# ESP-RC-Car-OLDPCB.net
KiCad netlist of a schematic drawn in Altium Designer
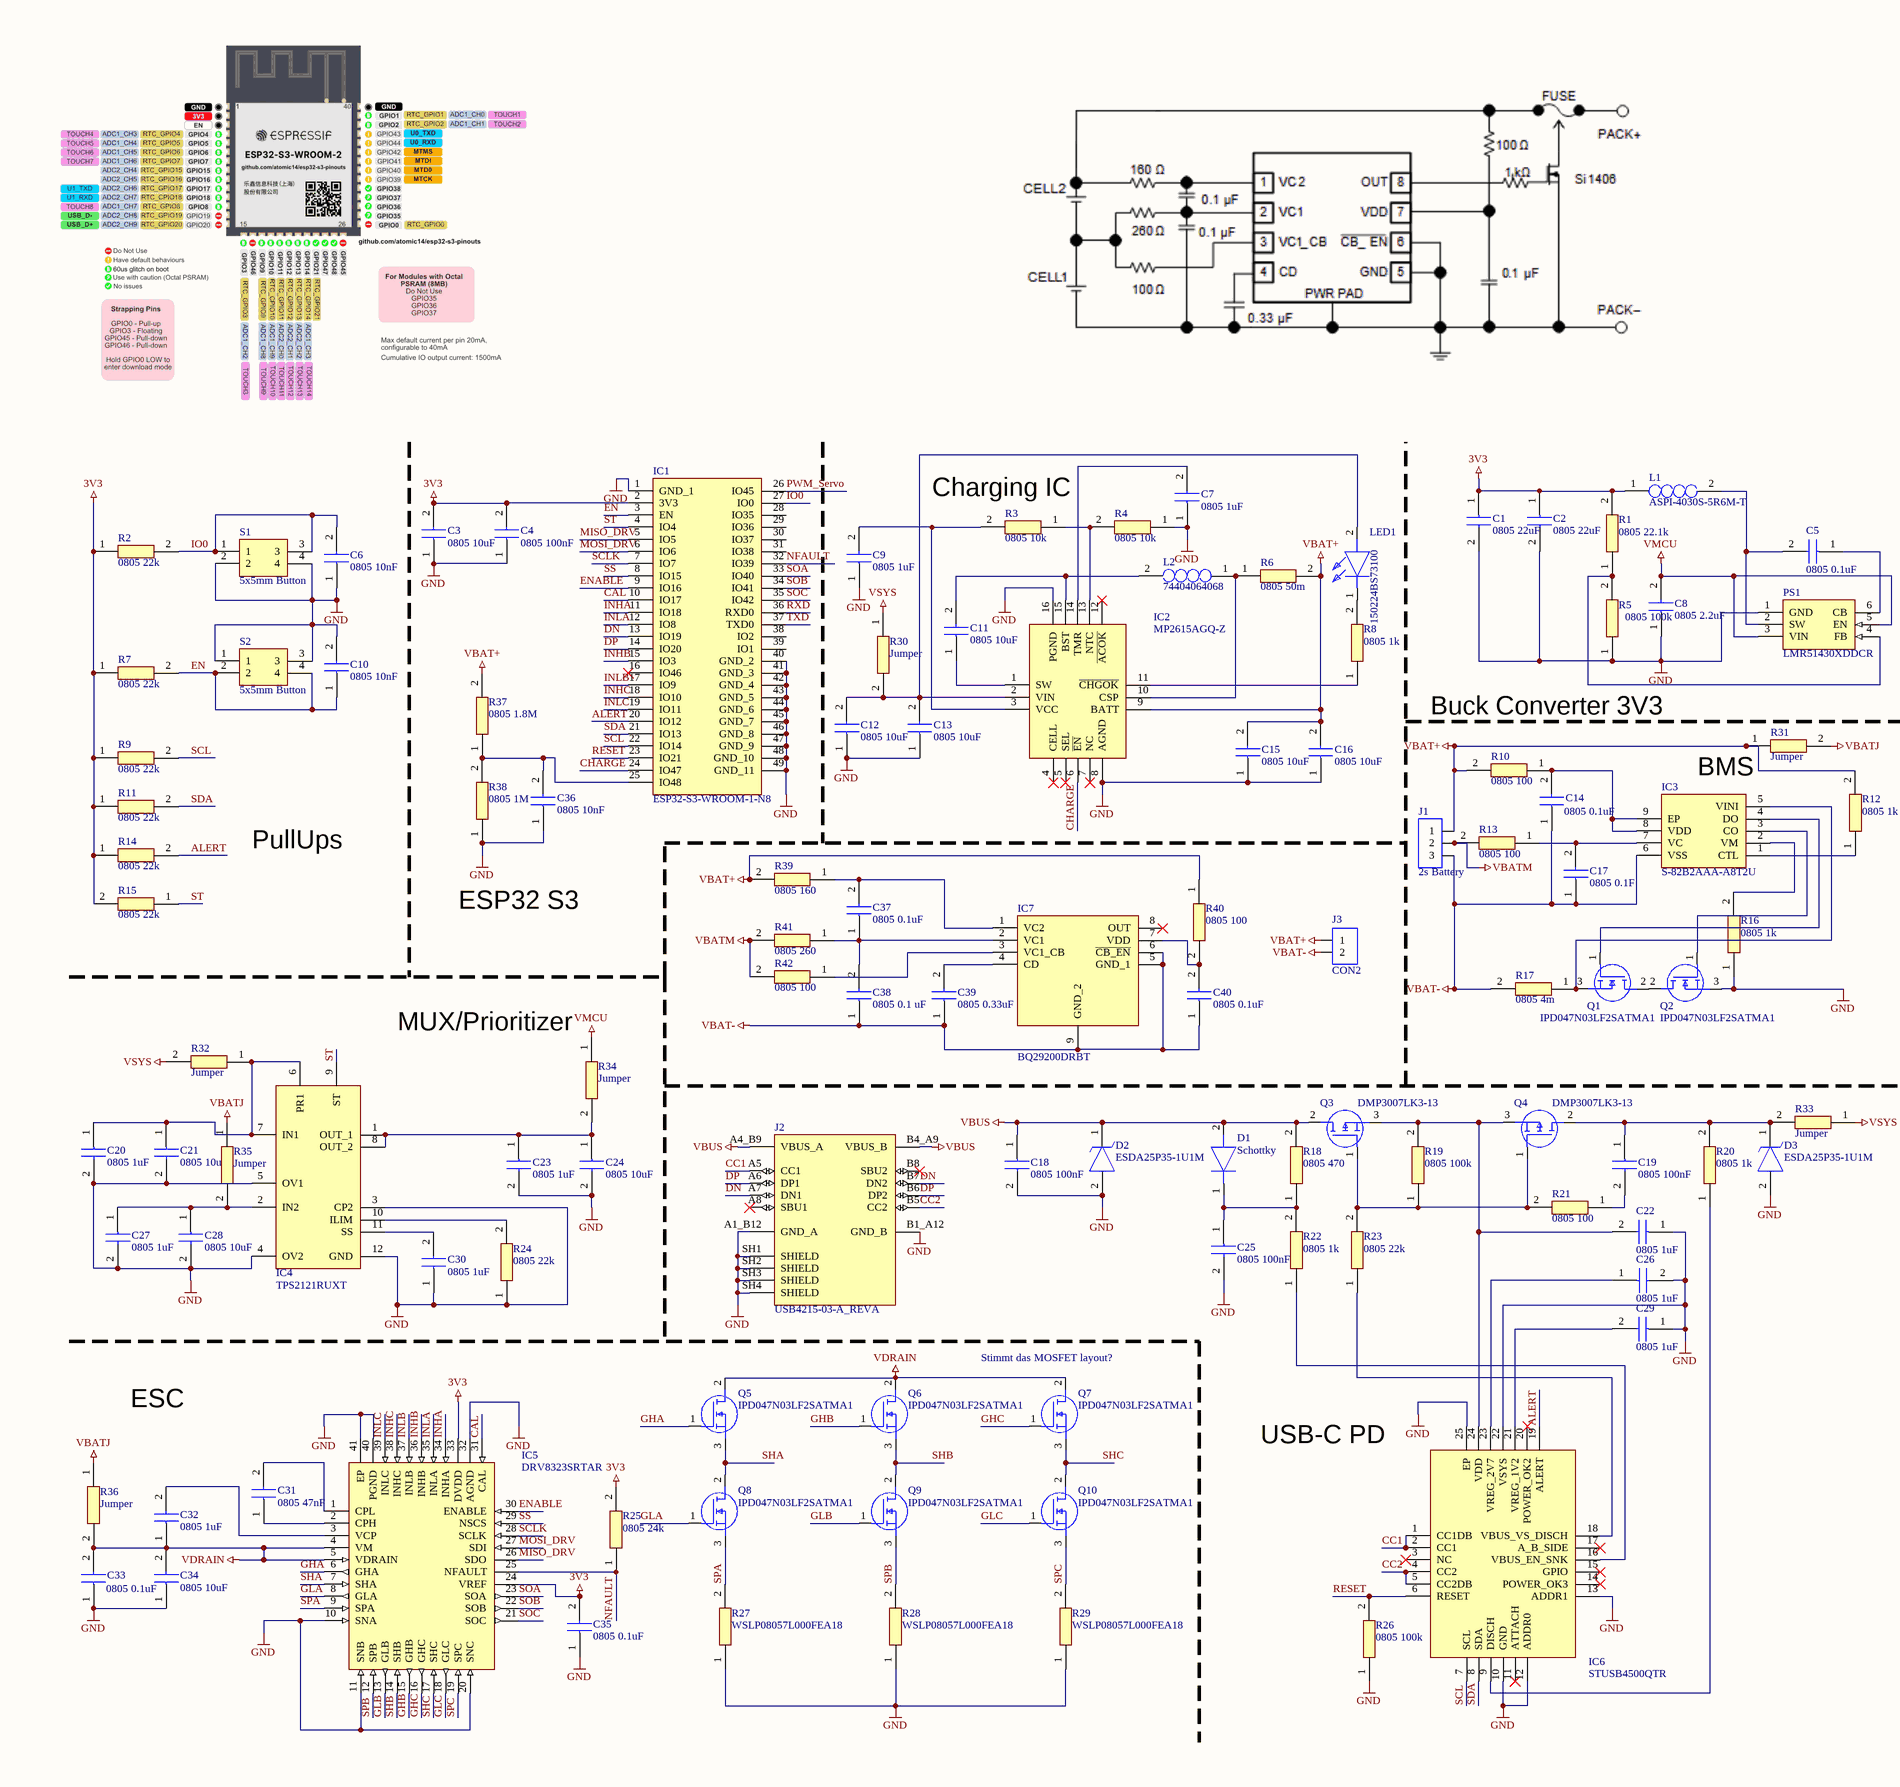
[diagram p0: ESP-RC-Car-OLDPCB.SchDoc, left]
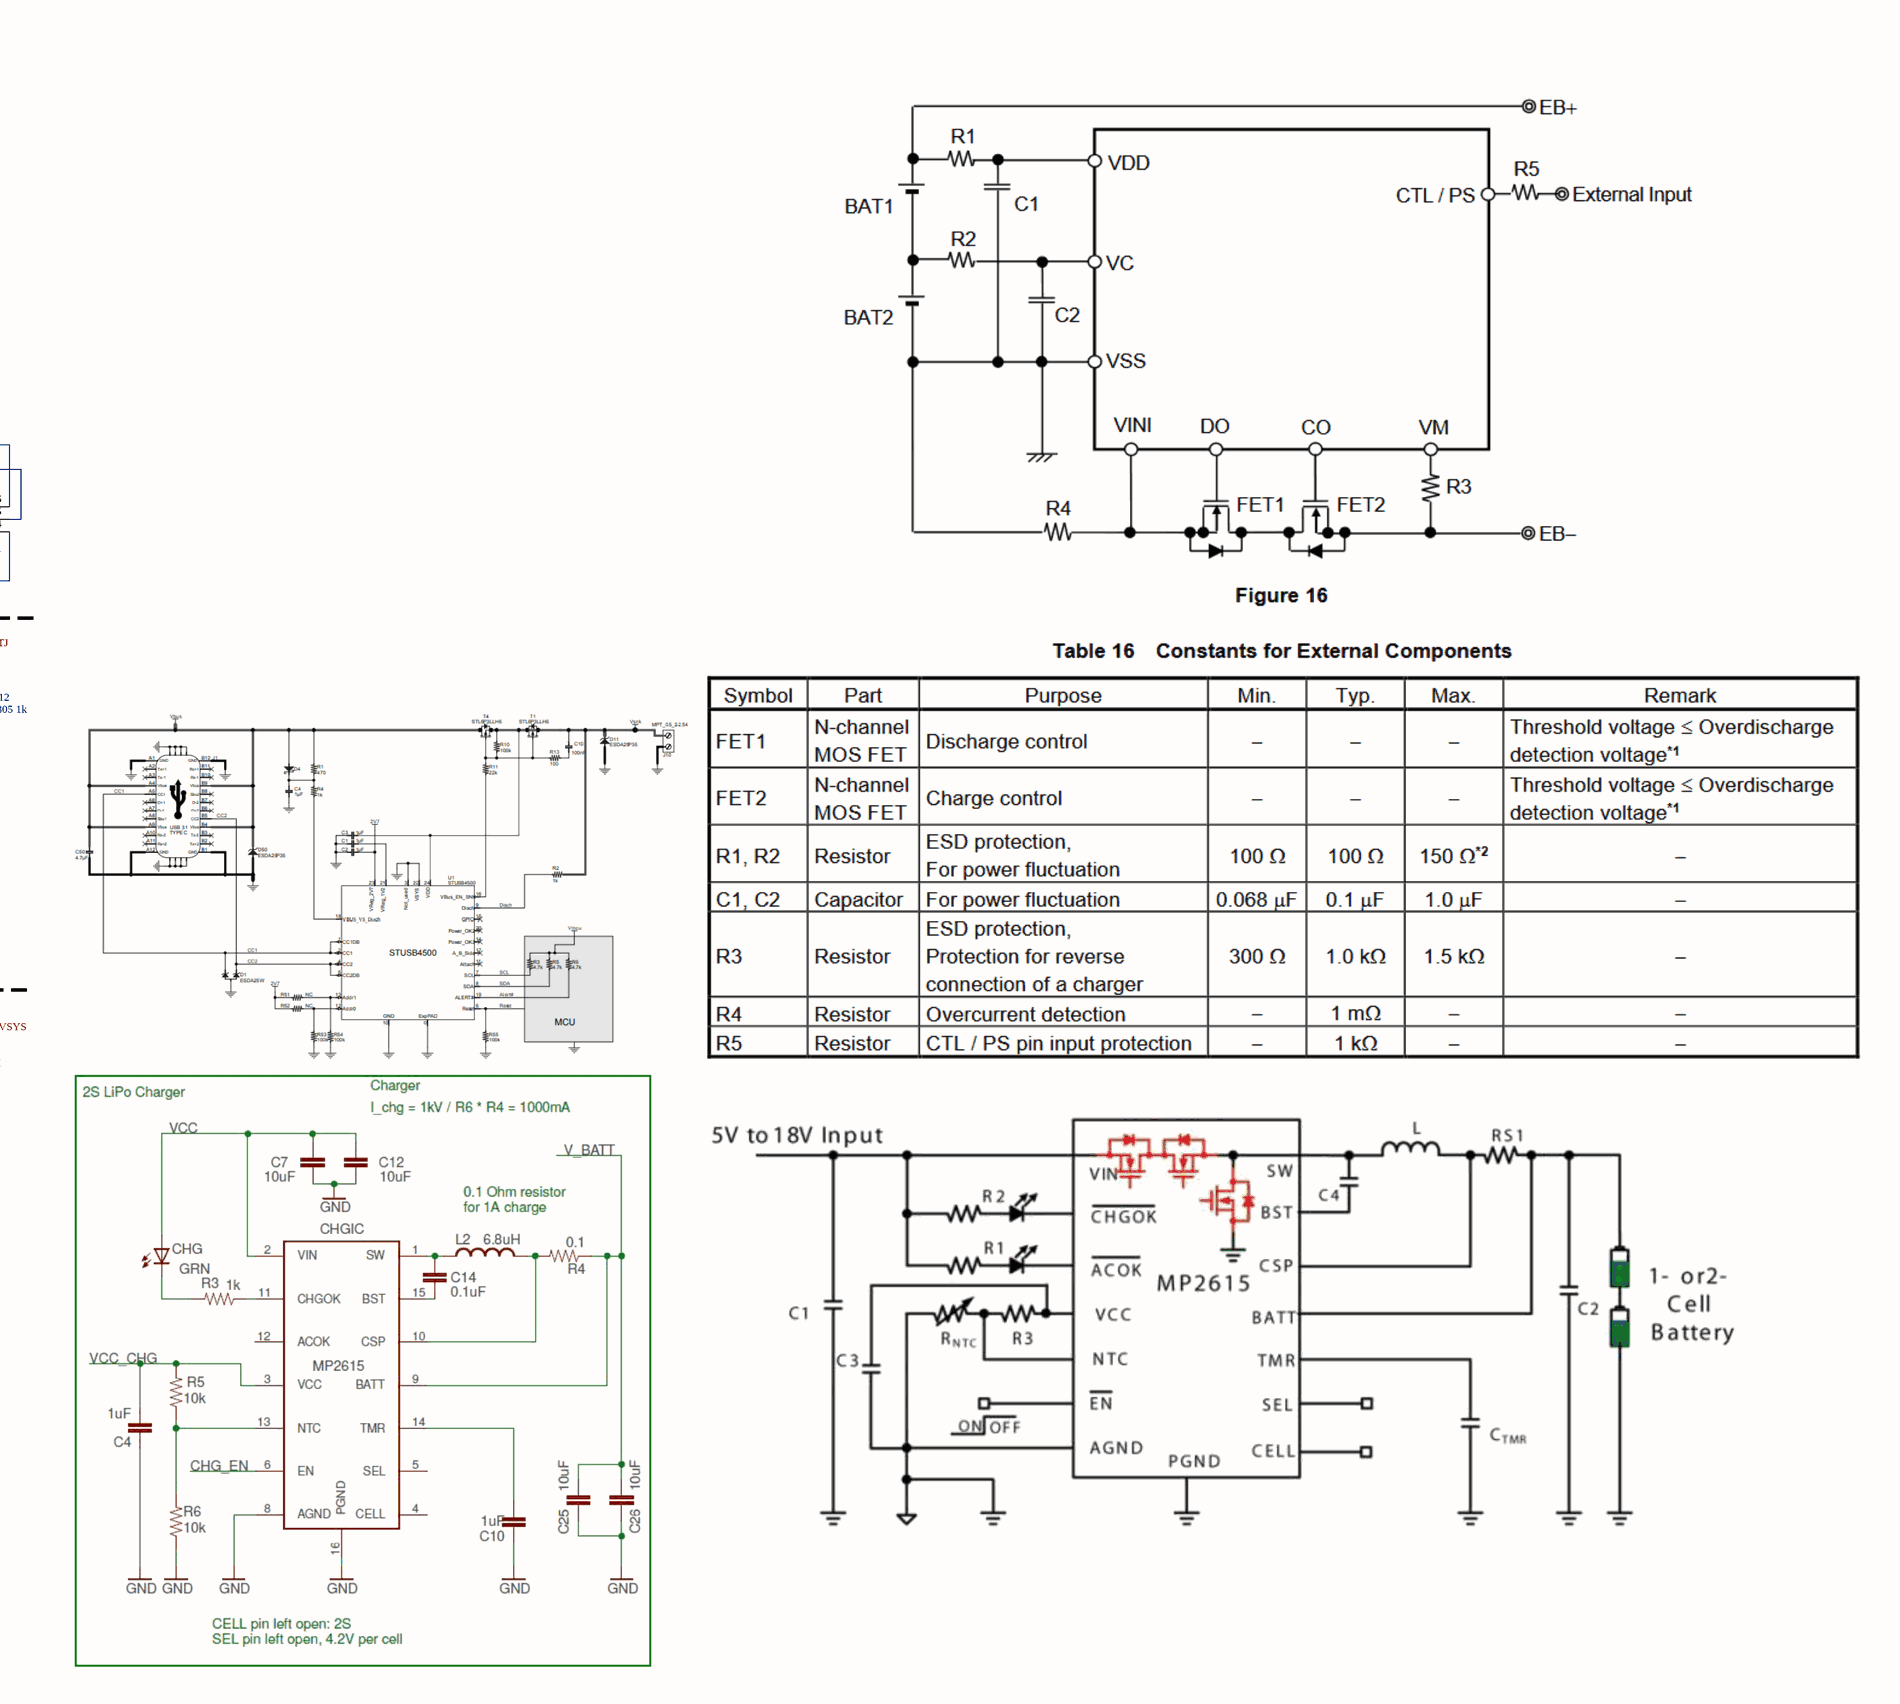
[diagram p1: ESP-RC-Car-OLDPCB.SchDoc, right]

(export (version "E")
  (design (tool "Eeschema 10.0.6"))
  (components
    (comp (ref "C1")
      (value "0805 22uF")
      (footprint "CAPC2012X94N")
      (description "Capacitor 25V")
      (fields
        (field (name "MANUFACTURER_PART_NUMBER") "08055A150JAT2A")
        (field (name "MOUSER PART NUMBER") "581-08055A150J")
      )
      (libsource (lib "*") (part "08055A150JAT2A"))
    )
    (comp (ref "C2")
      (value "0805 22uF")
      (footprint "CAPC2012X94N")
      (description "Capacitor 25V")
      (fields
        (field (name "MANUFACTURER_PART_NUMBER") "08055A150JAT2A")
        (field (name "MOUSER PART NUMBER") "581-08055A150J")
      )
      (libsource (lib "*") (part "08055A150JAT2A"))
    )
    (comp (ref "C3")
      (value "0805 10uF")
      (footprint "CAPC2012X94N")
      (description "Capacitor")
      (fields
        (field (name "MANUFACTURER_PART_NUMBER") "08055A150JAT2A")
        (field (name "MOUSER PART NUMBER") "581-08055A150J")
      )
      (libsource (lib "*") (part "08055A150JAT2A"))
    )
    (comp (ref "C4")
      (value "0805 100nF")
      (footprint "CAPC2012X94N")
      (description "Capacitor")
      (fields
        (field (name "MANUFACTURER_PART_NUMBER") "08055A150JAT2A")
        (field (name "MOUSER PART NUMBER") "581-08055A150J")
      )
      (libsource (lib "*") (part "08055A150JAT2A"))
    )
    (comp (ref "C5")
      (value "0805 0.1uF")
      (footprint "CAPC2012X94N")
      (description "Capacitor")
      (fields
        (field (name "MANUFACTURER_PART_NUMBER") "08055A150JAT2A")
        (field (name "MOUSER PART NUMBER") "581-08055A150J")
      )
      (libsource (lib "*") (part "08055A150JAT2A"))
    )
    (comp (ref "C6")
      (value "0805 10nF")
      (footprint "CAPC2012X94N")
      (description "Capacitor")
      (fields
        (field (name "MANUFACTURER_PART_NUMBER") "08055A150JAT2A")
        (field (name "MOUSER PART NUMBER") "581-08055A150J")
      )
      (libsource (lib "*") (part "08055A150JAT2A"))
    )
    (comp (ref "C7")
      (value "0805 1uF")
      (footprint "CAPC2012X94N")
      (description "Capacitor")
      (fields
        (field (name "MANUFACTURER_PART_NUMBER") "08055A150JAT2A")
        (field (name "MOUSER PART NUMBER") "581-08055A150J")
      )
      (libsource (lib "*") (part "08055A150JAT2A"))
    )
    (comp (ref "C8")
      (value "0805 2.2uF")
      (footprint "CAPC2012X94N")
      (description "Capacitor")
      (fields
        (field (name "MANUFACTURER_PART_NUMBER") "08055A150JAT2A")
        (field (name "MOUSER PART NUMBER") "581-08055A150J")
      )
      (libsource (lib "*") (part "08055A150JAT2A"))
    )
    (comp (ref "C9")
      (value "0805 1uF")
      (footprint "CAPC2012X94N")
      (description "Capacitor")
      (fields
        (field (name "MANUFACTURER_PART_NUMBER") "08055A150JAT2A")
        (field (name "MOUSER PART NUMBER") "581-08055A150J")
      )
      (libsource (lib "*") (part "08055A150JAT2A"))
    )
    (comp (ref "C10")
      (value "0805 10nF")
      (footprint "CAPC2012X94N")
      (description "Capacitor")
      (fields
        (field (name "MANUFACTURER_PART_NUMBER") "08055A150JAT2A")
        (field (name "MOUSER PART NUMBER") "581-08055A150J")
      )
      (libsource (lib "*") (part "08055A150JAT2A"))
    )
    (comp (ref "C11")
      (value "0805 10uF")
      (footprint "CAPC2012X94N")
      (description "Capacitor")
      (fields
        (field (name "MANUFACTURER_PART_NUMBER") "08055A150JAT2A")
        (field (name "MOUSER PART NUMBER") "581-08055A150J")
      )
      (libsource (lib "*") (part "08055A150JAT2A"))
    )
    (comp (ref "C12")
      (value "0805 10uF")
      (footprint "CAPC2012X94N")
      (description "Capacitor")
      (fields
        (field (name "MANUFACTURER_PART_NUMBER") "08055A150JAT2A")
        (field (name "MOUSER PART NUMBER") "581-08055A150J")
      )
      (libsource (lib "*") (part "08055A150JAT2A"))
    )
    (comp (ref "C13")
      (value "0805 10uF")
      (footprint "CAPC2012X94N")
      (description "Capacitor")
      (fields
        (field (name "MANUFACTURER_PART_NUMBER") "08055A150JAT2A")
        (field (name "MOUSER PART NUMBER") "581-08055A150J")
      )
      (libsource (lib "*") (part "08055A150JAT2A"))
    )
    (comp (ref "C14")
      (value "0805 0.1uF")
      (footprint "CAPC2012X94N")
      (description "Capacitor")
      (fields
        (field (name "MANUFACTURER_PART_NUMBER") "08055A150JAT2A")
        (field (name "MOUSER PART NUMBER") "581-08055A150J")
      )
      (libsource (lib "*") (part "08055A150JAT2A"))
    )
    (comp (ref "C15")
      (value "0805 10uF")
      (footprint "CAPC2012X94N")
      (description "Capacitor")
      (fields
        (field (name "MANUFACTURER_PART_NUMBER") "08055A150JAT2A")
        (field (name "MOUSER PART NUMBER") "581-08055A150J")
      )
      (libsource (lib "*") (part "08055A150JAT2A"))
    )
    (comp (ref "C16")
      (value "0805 10uF")
      (footprint "CAPC2012X94N")
      (description "Capacitor")
      (fields
        (field (name "MANUFACTURER_PART_NUMBER") "08055A150JAT2A")
        (field (name "MOUSER PART NUMBER") "581-08055A150J")
      )
      (libsource (lib "*") (part "08055A150JAT2A"))
    )
    (comp (ref "C17")
      (value "0805 0.1F")
      (footprint "CAPC2012X94N")
      (description "Capacitor")
      (fields
        (field (name "MANUFACTURER_PART_NUMBER") "08055A150JAT2A")
        (field (name "MOUSER PART NUMBER") "581-08055A150J")
      )
      (libsource (lib "*") (part "08055A150JAT2A"))
    )
    (comp (ref "C18")
      (value "0805 100nF")
      (footprint "CAPC2012X94N")
      (description "0805")
      (fields
        (field (name "MANUFACTURER_PART_NUMBER") "08055A150JAT2A")
        (field (name "MOUSER PART NUMBER") "581-08055A150J")
      )
      (libsource (lib "*") (part "08055A150JAT2A"))
    )
    (comp (ref "C19")
      (value "0805 100nF")
      (footprint "CAPC2012X94N")
      (description "0805")
      (fields
        (field (name "MANUFACTURER_PART_NUMBER") "08055A150JAT2A")
        (field (name "MOUSER PART NUMBER") "581-08055A150J")
      )
      (libsource (lib "*") (part "08055A150JAT2A"))
    )
    (comp (ref "C20")
      (value "0805 1uF")
      (footprint "CAPC2012X94N")
      (description "0805")
      (fields
        (field (name "MANUFACTURER_PART_NUMBER") "08055A150JAT2A")
        (field (name "MOUSER PART NUMBER") "581-08055A150J")
      )
      (libsource (lib "*") (part "08055A150JAT2A"))
    )
    (comp (ref "C21")
      (value "0805 10uF")
      (footprint "CAPC2012X94N")
      (description "0805")
      (fields
        (field (name "MANUFACTURER_PART_NUMBER") "08055A150JAT2A")
        (field (name "MOUSER PART NUMBER") "581-08055A150J")
      )
      (libsource (lib "*") (part "08055A150JAT2A"))
    )
    (comp (ref "C22")
      (value "0805 1uF")
      (footprint "CAPC2012X94N")
      (description "0805")
      (fields
        (field (name "MANUFACTURER_PART_NUMBER") "08055A150JAT2A")
        (field (name "MOUSER PART NUMBER") "581-08055A150J")
      )
      (libsource (lib "*") (part "08055A150JAT2A"))
    )
    (comp (ref "C23")
      (value "0805 1uF")
      (footprint "CAPC2012X94N")
      (description "0805")
      (fields
        (field (name "MANUFACTURER_PART_NUMBER") "08055A150JAT2A")
        (field (name "MOUSER PART NUMBER") "581-08055A150J")
      )
      (libsource (lib "*") (part "08055A150JAT2A"))
    )
    (comp (ref "C24")
      (value "0805 10uF")
      (footprint "CAPC2012X94N")
      (description "0805")
      (fields
        (field (name "MANUFACTURER_PART_NUMBER") "08055A150JAT2A")
        (field (name "MOUSER PART NUMBER") "581-08055A150J")
      )
      (libsource (lib "*") (part "08055A150JAT2A"))
    )
    (comp (ref "C25")
      (value "0805 100nF")
      (footprint "CAPC2012X94N")
      (description "0805")
      (fields
        (field (name "MANUFACTURER_PART_NUMBER") "08055A150JAT2A")
        (field (name "MOUSER PART NUMBER") "581-08055A150J")
      )
      (libsource (lib "*") (part "08055A150JAT2A"))
    )
    (comp (ref "C26")
      (value "0805 1uF")
      (footprint "CAPC2012X94N")
      (description "0805")
      (fields
        (field (name "MANUFACTURER_PART_NUMBER") "08055A150JAT2A")
        (field (name "MOUSER PART NUMBER") "581-08055A150J")
      )
      (libsource (lib "*") (part "08055A150JAT2A"))
    )
    (comp (ref "C27")
      (value "0805 1uF")
      (footprint "CAPC2012X94N")
      (description "0805")
      (fields
        (field (name "MANUFACTURER_PART_NUMBER") "08055A150JAT2A")
        (field (name "MOUSER PART NUMBER") "581-08055A150J")
      )
      (libsource (lib "*") (part "08055A150JAT2A"))
    )
    (comp (ref "C28")
      (value "0805 10uF")
      (footprint "CAPC2012X94N")
      (description "0805")
      (fields
        (field (name "MANUFACTURER_PART_NUMBER") "08055A150JAT2A")
        (field (name "MOUSER PART NUMBER") "581-08055A150J")
      )
      (libsource (lib "*") (part "08055A150JAT2A"))
    )
    (comp (ref "C29")
      (value "0805 1uF")
      (footprint "CAPC2012X94N")
      (description "0805")
      (fields
        (field (name "MANUFACTURER_PART_NUMBER") "08055A150JAT2A")
        (field (name "MOUSER PART NUMBER") "581-08055A150J")
      )
      (libsource (lib "*") (part "08055A150JAT2A"))
    )
    (comp (ref "C30")
      (value "0805 1uF")
      (footprint "CAPC2012X94N")
      (description "0805")
      (fields
        (field (name "MANUFACTURER_PART_NUMBER") "08055A150JAT2A")
        (field (name "MOUSER PART NUMBER") "581-08055A150J")
      )
      (libsource (lib "*") (part "08055A150JAT2A"))
    )
    (comp (ref "C31")
      (value "0805 47nF")
      (footprint "CAPC2012X94N")
      (description "0805")
      (fields
        (field (name "MANUFACTURER_PART_NUMBER") "08055A150JAT2A")
        (field (name "MOUSER PART NUMBER") "581-08055A150J")
      )
      (libsource (lib "*") (part "08055A150JAT2A"))
    )
    (comp (ref "C32")
      (value "0805 1uF")
      (footprint "CAPC2012X94N")
      (description "0805 16V X5R/X7R")
      (fields
        (field (name "MANUFACTURER_PART_NUMBER") "08055A150JAT2A")
        (field (name "MOUSER PART NUMBER") "581-08055A150J")
      )
      (libsource (lib "*") (part "08055A150JAT2A"))
    )
    (comp (ref "C33")
      (value "0805 0.1uF")
      (footprint "CAPC2012X94N")
      (description "0805 VM rated")
      (fields
        (field (name "MANUFACTURER_PART_NUMBER") "08055A150JAT2A")
        (field (name "MOUSER PART NUMBER") "581-08055A150J")
      )
      (libsource (lib "*") (part "08055A150JAT2A"))
    )
    (comp (ref "C34")
      (value "0805 10uF")
      (footprint "CAPC2012X94N")
      (description "0805")
      (fields
        (field (name "MANUFACTURER_PART_NUMBER") "08055A150JAT2A")
        (field (name "MOUSER PART NUMBER") "581-08055A150J")
      )
      (libsource (lib "*") (part "08055A150JAT2A"))
    )
    (comp (ref "C35")
      (value "0805 0.1uF")
      (footprint "CAPC2012X94N")
      (description "0805")
      (fields
        (field (name "MANUFACTURER_PART_NUMBER") "08055A150JAT2A")
        (field (name "MOUSER PART NUMBER") "581-08055A150J")
      )
      (libsource (lib "*") (part "08055A150JAT2A"))
    )
    (comp (ref "C36")
      (value "0805 10nF")
      (footprint "CAPC2012X94N")
      (description "Capacitor")
      (fields
        (field (name "MANUFACTURER_PART_NUMBER") "08055A150JAT2A")
        (field (name "MOUSER PART NUMBER") "581-08055A150J")
      )
      (libsource (lib "*") (part "08055A150JAT2A"))
    )
    (comp (ref "C37")
      (value "0805 0.1uF")
      (footprint "CAPC2012X94N")
      (description "Capacitor")
      (fields
        (field (name "MANUFACTURER_PART_NUMBER") "08055A150JAT2A")
        (field (name "MOUSER PART NUMBER") "581-08055A150J")
      )
      (libsource (lib "*") (part "08055A150JAT2A"))
    )
    (comp (ref "C38")
      (value "0805 0.1 uF")
      (footprint "CAPC2012X94N")
      (description "Capacitor")
      (fields
        (field (name "MANUFACTURER_PART_NUMBER") "08055A150JAT2A")
        (field (name "MOUSER PART NUMBER") "581-08055A150J")
      )
      (libsource (lib "*") (part "08055A150JAT2A"))
    )
    (comp (ref "C39")
      (value "0805 0.33uF")
      (footprint "CAPC2012X94N")
      (description "Capacitor")
      (fields
        (field (name "MANUFACTURER_PART_NUMBER") "08055A150JAT2A")
        (field (name "MOUSER PART NUMBER") "581-08055A150J")
      )
      (libsource (lib "*") (part "08055A150JAT2A"))
    )
    (comp (ref "C40")
      (value "0805 0.1uF")
      (footprint "CAPC2012X94N")
      (description "Capacitor")
      (fields
        (field (name "MANUFACTURER_PART_NUMBER") "08055A150JAT2A")
        (field (name "MOUSER PART NUMBER") "581-08055A150J")
      )
      (libsource (lib "*") (part "08055A150JAT2A"))
    )
    (comp (ref "D1")
      (value "Schottky")
      (footprint "SODFL3517X110N")
      (description "Schottky Diode")
      (fields (field (name "MANUFACTURER_PART_NUMBER") "PMEG3010ER"))
      (libsource (lib "*") (part "PMEG3010ER"))
    )
    (comp (ref "D2")
      (value "ESDA25P35-1U1M")
      (footprint "ESDA25P351U1M")
      (description "TVS Diode (Uni-directional)")
      (fields (field (name "MOUSER PART NUMBER") "511-ESDA25P35-1U1M"))
      (libsource (lib "*") (part "ESDA25P35-1U1M"))
    )
    (comp (ref "D3")
      (value "ESDA25P35-1U1M")
      (footprint "ESDA25P351U1M")
      (description "TVS Diode (Uni-directional)")
      (fields (field (name "MOUSER PART NUMBER") "511-ESDA25P35-1U1M"))
      (libsource (lib "*") (part "ESDA25P35-1U1M"))
    )
    (comp (ref "IC1")
      (value "ESP32-S3-WROOM-1-N8")
      (footprint "ESP32S3WROOM1N8R2")
      (description "Integrated Circuit")
      (fields (field (name "MOUSER PART NUMBER") "356-ESP32-S3WROOM1N8"))
      (libsource (lib "*") (part "ESP32-S3-WROOM-1-N8"))
    )
    (comp (ref "IC2")
      (value "MP2615AGQ-Z")
      (footprint "MP2615AGQZ")
      (description "Integrated Circuit")
      (fields (field (name "MOUSER PART NUMBER") "946-MP2615AGQ-Z"))
      (libsource (lib "*") (part "MP2615AGQ-Z"))
    )
    (comp (ref "IC3")
      (value "S-82B2AAA-A8T2U")
      (footprint "S82B2AAAA8T2U")
      (description "Integrated Circuit")
      (fields (field (name "MOUSER PART NUMBER") "628-S-82B2AAA-A8T2U"))
      (libsource (lib "*") (part "S-82B2AAA-A8T2U"))
    )
    (comp (ref "IC4")
      (value "TPS2121RUXT")
      (footprint "TPS2121RUXT")
      (description "Integrated Circuit")
      (fields (field (name "MOUSER PART NUMBER") "595-TPS2121RUXT"))
      (libsource (lib "*") (part "TPS2121RUXT"))
    )
    (comp (ref "IC5")
      (value "DRV8323SRTAR")
      (footprint "QFN50P600X600X80-41N-D")
      (description "Integrated Circuit")
      (fields (field (name "MOUSER PART NUMBER") "595-DRV8323SRTAR"))
      (libsource (lib "lib") (part "DRV8323SRTAR"))
    )
    (comp (ref "IC6")
      (value "STUSB4500QTR")
      (footprint "QFN50P400X400X100-25N-D")
      (description "Integrated Circuit")
      (fields (field (name "MOUSER PART NUMBER") "511-STUSB4500QTR"))
      (libsource (lib "*") (part "STUSB4500QTR"))
    )
    (comp (ref "IC7")
      (value "BQ29200DRBT")
      (footprint "SON65P300X300X100-9N-D")
      (description "Integrated Circuit")
      (fields (field (name "MOUSER PART NUMBER") "595-BQ29200DRBT"))
      (libsource (lib "*") (part "BQ29200DRBT"))
    )
    (comp (ref "J1")
      (value "2s Battery")
      (footprint "Sip-3")
      (description "Stecker")
      (libsource (lib "lib") (part "CON3"))
    )
    (comp (ref "J2")
      (value "USB4215-03-A_REVA")
      (footprint "GCT_USB4215-03-A_REVA")
      (fields (field (name "MF") "Global Connector Technology") (field (name "MP") "USB4215-03-A"))
      (libsource (lib "lib") (part "USB4215-03-A_REVA"))
    )
    (comp (ref "J3")
      (value "CON2")
      (footprint "SIP-2")
      (description "Stecker")
      (libsource (lib "lib") (part "CON2"))
    )
    (comp (ref "L1")
      (value "ASPI-4030S-5R6M-T")
      (footprint "ASPI-4030S")
      (description "Inductor")
      (fields (field (name "MOUSER PART NUMBER") "815-ASPI-4030S-5R6MT"))
      (libsource (lib "*") (part "ASPI-4030S-5R6M-T"))
    )
    (comp (ref "L2")
      (value "74404064068")
      (footprint "INDPM6060X450N")
      (description "Inductor")
      (fields (field (name "MOUSER PART NUMBER") "710-74404064068"))
      (libsource (lib "*") (part "74404064068"))
    )
    (comp (ref "LED1")
      (value "150224BS73100")
      (footprint "150224BS73100")
      (description "LED")
      (fields (field (name "MOUSER PART NUMBER") "710-150224BS73100"))
      (libsource (lib "*") (part "150224BS73100"))
    )
    (comp (ref "PS1")
      (value "LMR51430XDDCR")
      (footprint "SOT95P280X110-6N")
      (description "Power Supply 500kHz")
      (fields (field (name "MOUSER PART NUMBER") "595-LMR51430XDDCR"))
      (libsource (lib "*") (part "LMR51430XDDCR"))
    )
    (comp (ref "Q1")
      (value "IPD047N03LF2SATMA1")
      (footprint "IPD047N03LF2SATMA1")
      (description "MOSFET (N-Channel)")
      (fields (field (name "MOUSER PART NUMBER") "726-IPD047N03LF2SATM"))
      (libsource (lib "*") (part "IPD047N03LF2SATMA1"))
    )
    (comp (ref "Q2")
      (value "IPD047N03LF2SATMA1")
      (footprint "IPD047N03LF2SATMA1")
      (description "MOSFET (N-Channel)")
      (fields (field (name "MOUSER PART NUMBER") "726-IPD047N03LF2SATM"))
      (libsource (lib "*") (part "IPD047N03LF2SATMA1"))
    )
    (comp (ref "Q3")
      (value "DMP3007LK3-13")
      (footprint "DMP3007LK313")
      (description "MOSFET (P-Channel)")
      (fields (field (name "MOUSER PART NUMBER") "621-DMP3007LK3-13"))
      (libsource (lib "*") (part "DMP3007LK3-13"))
    )
    (comp (ref "Q4")
      (value "DMP3007LK3-13")
      (footprint "DMP3007LK313")
      (description "MOSFET (P-Channel)")
      (fields (field (name "MOUSER PART NUMBER") "621-DMP3007LK3-13"))
      (libsource (lib "*") (part "DMP3007LK3-13"))
    )
    (comp (ref "Q5")
      (value "IPD047N03LF2SATMA1")
      (footprint "IPD047N03LF2SATMA1")
      (description "MOSFET (N-Channel)")
      (fields (field (name "MOUSER PART NUMBER") "726-IPD047N03LF2SATM"))
      (libsource (lib "*") (part "IPD047N03LF2SATMA1"))
    )
    (comp (ref "Q6")
      (value "IPD047N03LF2SATMA1")
      (footprint "IPD047N03LF2SATMA1")
      (description "MOSFET (N-Channel)")
      (fields (field (name "MOUSER PART NUMBER") "726-IPD047N03LF2SATM"))
      (libsource (lib "*") (part "IPD047N03LF2SATMA1"))
    )
    (comp (ref "Q7")
      (value "IPD047N03LF2SATMA1")
      (footprint "IPD047N03LF2SATMA1")
      (description "MOSFET (N-Channel)")
      (fields (field (name "MOUSER PART NUMBER") "726-IPD047N03LF2SATM"))
      (libsource (lib "*") (part "IPD047N03LF2SATMA1"))
    )
    (comp (ref "Q8")
      (value "IPD047N03LF2SATMA1")
      (footprint "IPD047N03LF2SATMA1")
      (description "MOSFET (N-Channel)")
      (fields (field (name "MOUSER PART NUMBER") "726-IPD047N03LF2SATM"))
      (libsource (lib "*") (part "IPD047N03LF2SATMA1"))
    )
    (comp (ref "Q9")
      (value "IPD047N03LF2SATMA1")
      (footprint "IPD047N03LF2SATMA1")
      (description "MOSFET (N-Channel)")
      (fields (field (name "MOUSER PART NUMBER") "726-IPD047N03LF2SATM"))
      (libsource (lib "*") (part "IPD047N03LF2SATMA1"))
    )
    (comp (ref "Q10")
      (value "IPD047N03LF2SATMA1")
      (footprint "IPD047N03LF2SATMA1")
      (description "MOSFET (N-Channel)")
      (fields (field (name "MOUSER PART NUMBER") "726-IPD047N03LF2SATM"))
      (libsource (lib "*") (part "IPD047N03LF2SATMA1"))
    )
    (comp (ref "R1")
      (value "0805 22.1k")
      (footprint "RESC2012X65N")
      (description "Resistor low tolerance")
      (fields (field (name "MANUFACTURER_PART_NUMBER") "CPF0805B102RE1"))
      (libsource (lib "") (part "CPF0805B102RE1_2"))
    )
    (comp (ref "R2")
      (value "0805 22k")
      (footprint "RESC2012X65N")
      (description "Resistor")
      (fields (field (name "MANUFACTURER_PART_NUMBER") "CPF0805B102RE1"))
      (libsource (lib "") (part "CPF0805B102RE1_3"))
    )
    (comp (ref "R3")
      (value "0805 10k")
      (footprint "RESC2012X65N")
      (description "Resistor low tolerance")
      (fields (field (name "MANUFACTURER_PART_NUMBER") "CPF0805B102RE1"))
      (libsource (lib "") (part "CPF0805B102RE1_1"))
    )
    (comp (ref "R4")
      (value "0805 10k")
      (footprint "RESC2012X65N")
      (description "Resistor low tolerance")
      (fields (field (name "MANUFACTURER_PART_NUMBER") "CPF0805B102RE1"))
      (libsource (lib "") (part "CPF0805B102RE1_1"))
    )
    (comp (ref "R5")
      (value "0805 100k")
      (footprint "RESC2012X65N")
      (description "Resistor low tolerance")
      (fields (field (name "MANUFACTURER_PART_NUMBER") "CPF0805B102RE1"))
      (libsource (lib "") (part "CPF0805B102RE1_2"))
    )
    (comp (ref "R6")
      (value "0805 50m")
      (footprint "RESC2012X65N")
      (description "Resistor low tolerance")
      (fields (field (name "MANUFACTURER_PART_NUMBER") "CPF0805B102RE1"))
      (libsource (lib "") (part "CPF0805B102RE1_3"))
    )
    (comp (ref "R7")
      (value "0805 22k")
      (footprint "RESC2012X65N")
      (description "Resistor")
      (fields (field (name "MANUFACTURER_PART_NUMBER") "CPF0805B102RE1"))
      (libsource (lib "") (part "CPF0805B102RE1_3"))
    )
    (comp (ref "R8")
      (value "0805 1k")
      (footprint "RESC2012X65N")
      (description "Resistor low tolerance")
      (fields (field (name "MANUFACTURER_PART_NUMBER") "CPF0805B102RE1"))
      (libsource (lib "") (part "CPF0805B102RE1_2"))
    )
    (comp (ref "R9")
      (value "0805 22k")
      (footprint "RESC2012X65N")
      (description "Resistor")
      (fields (field (name "MANUFACTURER_PART_NUMBER") "CPF0805B102RE1"))
      (libsource (lib "") (part "CPF0805B102RE1_3"))
    )
    (comp (ref "R10")
      (value "0805 100")
      (footprint "RESC2012X65N")
      (description "Resistor low tolerance")
      (fields (field (name "MANUFACTURER_PART_NUMBER") "CPF0805B102RE1"))
      (libsource (lib "") (part "CPF0805B102RE1_1"))
    )
    (comp (ref "R11")
      (value "0805 22k")
      (footprint "RESC2012X65N")
      (description "Resistor")
      (fields (field (name "MANUFACTURER_PART_NUMBER") "CPF0805B102RE1"))
      (libsource (lib "") (part "CPF0805B102RE1_3"))
    )
    (comp (ref "R12")
      (value "0805 1k")
      (footprint "RESC2012X65N")
      (description "Resistor low tolerance")
      (fields (field (name "MANUFACTURER_PART_NUMBER") "CPF0805B102RE1"))
      (libsource (lib "") (part "CPF0805B102RE1_2"))
    )
    (comp (ref "R13")
      (value "0805 100")
      (footprint "RESC2012X65N")
      (description "Resistor low tolerance")
      (fields (field (name "MANUFACTURER_PART_NUMBER") "CPF0805B102RE1"))
      (libsource (lib "") (part "CPF0805B102RE1_1"))
    )
    (comp (ref "R14")
      (value "0805 22k")
      (footprint "RESC2012X65N")
      (description "Resistor")
      (fields (field (name "MANUFACTURER_PART_NUMBER") "CPF0805B102RE1"))
      (libsource (lib "") (part "CPF0805B102RE1_3"))
    )
    (comp (ref "R15")
      (value "0805 22k")
      (footprint "RESC2012X65N")
      (description "Resistor")
      (fields (field (name "MANUFACTURER_PART_NUMBER") "CPF0805B102RE1"))
      (libsource (lib "") (part "CPF0805B102RE1_1"))
    )
    (comp (ref "R16")
      (value "0805 1k")
      (footprint "RESC2012X65N")
      (description "Resistor low tolerance")
      (fields (field (name "MANUFACTURER_PART_NUMBER") "CPF0805B102RE1"))
      (libsource (lib "") (part "CPF0805B102RE1_2"))
    )
    (comp (ref "R17")
      (value "0805 4m")
      (footprint "RESC2012X65N")
      (description "Resistor low tolerance")
      (fields (field (name "MANUFACTURER_PART_NUMBER") "CPF0805B102RE1"))
      (libsource (lib "") (part "CPF0805B102RE1_1"))
    )
    (comp (ref "R18")
      (value "0805 470")
      (footprint "RESC2012X65N")
      (description "Resistor")
      (fields (field (name "MANUFACTURER_PART_NUMBER") "CPF0805B102RE1"))
      (libsource (lib "") (part "CPF0805B102RE1_2"))
    )
    (comp (ref "R19")
      (value "0805 100k")
      (footprint "RESC2012X65N")
      (description "Resistor")
      (fields (field (name "MANUFACTURER_PART_NUMBER") "CPF0805B102RE1"))
      (libsource (lib "") (part "CPF0805B102RE1_2"))
    )
    (comp (ref "R20")
      (value "0805 1k")
      (footprint "RESC2012X65N")
      (description "Resistor")
      (fields (field (name "MANUFACTURER_PART_NUMBER") "CPF0805B102RE1"))
      (libsource (lib "") (part "CPF0805B102RE1_2"))
    )
    (comp (ref "R21")
      (value "0805 100")
      (footprint "RESC2012X65N")
      (description "Resistor")
      (fields (field (name "MANUFACTURER_PART_NUMBER") "CPF0805B102RE1"))
      (libsource (lib "") (part "CPF0805B102RE1_1"))
    )
    (comp (ref "R22")
      (value "0805 1k")
      (footprint "RESC2012X65N")
      (description "Resistor")
      (fields (field (name "MANUFACTURER_PART_NUMBER") "CPF0805B102RE1"))
      (libsource (lib "") (part "CPF0805B102RE1_2"))
    )
    (comp (ref "R23")
      (value "0805 22k")
      (footprint "RESC2012X65N")
      (description "Resistor")
      (fields (field (name "MANUFACTURER_PART_NUMBER") "CPF0805B102RE1"))
      (libsource (lib "") (part "CPF0805B102RE1_2"))
    )
    (comp (ref "R24")
      (value "0805 22k")
      (footprint "RESC2012X65N")
      (description "Resistor")
      (fields (field (name "MANUFACTURER_PART_NUMBER") "CPF0805B102RE1"))
      (libsource (lib "") (part "CPF0805B102RE1_2"))
    )
    (comp (ref "R25")
      (value "0805 24k")
      (footprint "RESC2012X65N")
      (description "Resistor")
      (fields (field (name "MANUFACTURER_PART_NUMBER") "CPF0805B102RE1"))
      (libsource (lib "") (part "CPF0805B102RE1_2"))
    )
    (comp (ref "R26")
      (value "0805 100k")
      (footprint "RESC2012X65N")
      (description "Resistor")
      (fields (field (name "MANUFACTURER_PART_NUMBER") "CPF0805B102RE1"))
      (libsource (lib "") (part "CPF0805B102RE1_2"))
    )
    (comp (ref "R27")
      (value "WSLP08057L000FEA18")
      (footprint "RESC2013X58N")
      (description "Resistor")
      (fields (field (name "MOUSER PART NUMBER") "71-WSLP08057L000FEA1"))
      (libsource (lib "*") (part "WSLP08057L000FEA18"))
    )
    (comp (ref "R28")
      (value "WSLP08057L000FEA18")
      (footprint "RESC2013X58N")
      (description "Resistor")
      (fields (field (name "MOUSER PART NUMBER") "71-WSLP08057L000FEA1"))
      (libsource (lib "*") (part "WSLP08057L000FEA18"))
    )
    (comp (ref "R29")
      (value "WSLP08057L000FEA18")
      (footprint "RESC2013X58N")
      (description "Resistor")
      (fields (field (name "MOUSER PART NUMBER") "71-WSLP08057L000FEA1"))
      (libsource (lib "*") (part "WSLP08057L000FEA18"))
    )
    (comp (ref "R30")
      (value "Jumper")
      (footprint "Solder Jumper 5A")
      (description "Resistor")
      (fields (field (name "MANUFACTURER_PART_NUMBER") "CPF0805B102RE1"))
      (libsource (lib "*") (part "CPF0805B102RE1"))
    )
    (comp (ref "R31")
      (value "Jumper")
      (footprint "Solder Jumper 9A")
      (description "Resistor")
      (fields (field (name "MANUFACTURER_PART_NUMBER") "CPF0805B102RE1"))
      (libsource (lib "") (part "CPF0805B102RE1_3"))
    )
    (comp (ref "R32")
      (value "Jumper")
      (footprint "Solder Jumper 5A")
      (description "Resistor")
      (fields (field (name "MANUFACTURER_PART_NUMBER") "CPF0805B102RE1"))
      (libsource (lib "") (part "CPF0805B102RE1_1"))
    )
    (comp (ref "R33")
      (value "Jumper")
      (footprint "Solder Jumper 5A")
      (description "Resistor")
      (fields (field (name "MANUFACTURER_PART_NUMBER") "CPF0805B102RE1"))
      (libsource (lib "") (part "CPF0805B102RE1_1"))
    )
    (comp (ref "R34")
      (value "Jumper")
      (footprint "Solder Jumper 5A")
      (description "Resistor")
      (fields (field (name "MANUFACTURER_PART_NUMBER") "CPF0805B102RE1"))
      (libsource (lib "*") (part "CPF0805B102RE1"))
    )
    (comp (ref "R35")
      (value "Jumper")
      (footprint "Solder Jumper 5A")
      (description "Resistor")
      (fields (field (name "MANUFACTURER_PART_NUMBER") "CPF0805B102RE1"))
      (libsource (lib "*") (part "CPF0805B102RE1"))
    )
    (comp (ref "R36")
      (value "Jumper")
      (footprint "Solder Jumper 9A")
      (description "Resistor")
      (fields (field (name "MANUFACTURER_PART_NUMBER") "CPF0805B102RE1"))
      (libsource (lib "*") (part "CPF0805B102RE1"))
    )
    (comp (ref "R37")
      (value "0805 1.8M")
      (footprint "RESC2012X65N")
      (description "Resistor")
      (fields (field (name "MANUFACTURER_PART_NUMBER") "CPF0805B102RE1"))
      (libsource (lib "") (part "CPF0805B102RE1_2"))
    )
    (comp (ref "R38")
      (value "0805 1M")
      (footprint "RESC2012X65N")
      (description "Resistor")
      (fields (field (name "MANUFACTURER_PART_NUMBER") "CPF0805B102RE1"))
      (libsource (lib "") (part "CPF0805B102RE1_2"))
    )
    (comp (ref "R39")
      (value "0805 160")
      (footprint "RESC2012X65N")
      (description "Resistor low tolerance")
      (fields (field (name "MANUFACTURER_PART_NUMBER") "CPF0805B102RE1"))
      (libsource (lib "") (part "CPF0805B102RE1_1"))
    )
    (comp (ref "R40")
      (value "0805 100")
      (footprint "RESC2012X65N")
      (description "Resistor low tolerance")
      (fields (field (name "MANUFACTURER_PART_NUMBER") "CPF0805B102RE1"))
      (libsource (lib "*") (part "CPF0805B102RE1"))
    )
    (comp (ref "R41")
      (value "0805 260")
      (footprint "RESC2012X65N")
      (description "Resistor low tolerance")
      (fields (field (name "MANUFACTURER_PART_NUMBER") "CPF0805B102RE1"))
      (libsource (lib "") (part "CPF0805B102RE1_1"))
    )
    (comp (ref "R42")
      (value "0805 100")
      (footprint "RESC2012X65N")
      (description "Resistor low tolerance")
      (fields (field (name "MANUFACTURER_PART_NUMBER") "CPF0805B102RE1"))
      (libsource (lib "") (part "CPF0805B102RE1_1"))
    )
    (comp (ref "S1")
      (value "5x5mm Button")
      (footprint "430182070816")
      (description "Switch")
      (fields
        (field (name "MANUFACTURER_PART_NUMBER") "430182050816")
        (field (name "MOUSER PART NUMBER") "710-430182050816")
      )
      (libsource (lib "*") (part "430182050816"))
    )
    (comp (ref "S2")
      (value "5x5mm Button")
      (footprint "430182070816")
      (description "Switch")
      (fields
        (field (name "MANUFACTURER_PART_NUMBER") "430182050816")
        (field (name "MOUSER PART NUMBER") "710-430182050816")
      )
      (libsource (lib "*") (part "430182050816"))
    )
  )
  (nets
    (net (code "1") (name "/ALERT") (class "Default")
      (node (ref "IC1") (pin "20") (pinfunction "IO12_20") (pintype "passive"))
      (node (ref "IC6") (pin "19") (pinfunction "ALERT_19") (pintype "passive"))
      (node (ref "R14") (pin "2") (pinfunction "2_2") (pintype "passive"))
    )
    (net (code "2") (name "/CAL") (class "Default")
      (node (ref "IC1") (pin "10") (pinfunction "IO17_10") (pintype "passive"))
      (node (ref "IC5") (pin "31") (pinfunction "CAL_31") (pintype "input"))
    )
    (net (code "3") (name "/CC1") (class "Default")
      (node (ref "IC6") (pin "1") (pinfunction "CC1DB_1") (pintype "passive"))
      (node (ref "IC6") (pin "2") (pinfunction "CC1_2") (pintype "passive"))
      (node (ref "J2") (pin "A5") (pinfunction "CC1_A5") (pintype "bidirectional"))
    )
    (net (code "4") (name "/CC2") (class "Default")
      (node (ref "IC6") (pin "4") (pinfunction "CC2_4") (pintype "passive"))
      (node (ref "IC6") (pin "5") (pinfunction "CC2DB_5") (pintype "passive"))
      (node (ref "J2") (pin "B5") (pinfunction "CC2_B5") (pintype "bidirectional"))
    )
    (net (code "5") (name "/CHARGE") (class "Default")
      (node (ref "IC1") (pin "24") (pinfunction "IO47_24") (pintype "passive"))
      (node (ref "IC2") (pin "6") (pinfunction "~{EN}_6") (pintype "passive"))
    )
    (net (code "6") (name "/DN") (class "Default")
      (node (ref "IC1") (pin "13") (pinfunction "IO19_13") (pintype "passive"))
      (node (ref "J2") (pin "A7") (pinfunction "DN1_A7") (pintype "bidirectional"))
      (node (ref "J2") (pin "B7") (pinfunction "DN2_B7") (pintype "bidirectional"))
    )
    (net (code "7") (name "/DP") (class "Default")
      (node (ref "IC1") (pin "14") (pinfunction "IO20_14") (pintype "passive"))
      (node (ref "J2") (pin "A6") (pinfunction "DP1_A6") (pintype "bidirectional"))
      (node (ref "J2") (pin "B6") (pinfunction "DP2_B6") (pintype "bidirectional"))
    )
    (net (code "8") (name "/EN") (class "Default")
      (node (ref "C10") (pin "1") (pinfunction "1_1") (pintype "passive"))
      (node (ref "IC1") (pin "3") (pinfunction "EN_3") (pintype "passive"))
      (node (ref "R7") (pin "2") (pinfunction "2_2") (pintype "passive"))
      (node (ref "S2") (pin "2") (pinfunction "2_2") (pintype "passive"))
      (node (ref "S2") (pin "4") (pinfunction "4_4") (pintype "passive"))
    )
    (net (code "9") (name "/ENABLE") (class "Default")
      (node (ref "IC1") (pin "9") (pinfunction "IO16_9") (pintype "passive"))
      (node (ref "IC5") (pin "30") (pinfunction "ENABLE_30") (pintype "input"))
    )
    (net (code "10") (name "/GHA") (class "Default")
      (node (ref "IC5") (pin "6") (pinfunction "GHA_6") (pintype "output"))
      (node (ref "Q5") (pin "1") (pinfunction "G_1") (pintype "passive"))
    )
    (net (code "11") (name "/GHB") (class "Default")
      (node (ref "IC5") (pin "15") (pinfunction "GHB_15") (pintype "output"))
      (node (ref "Q6") (pin "1") (pinfunction "G_1") (pintype "passive"))
    )
    (net (code "12") (name "/GHC") (class "Default")
      (node (ref "IC5") (pin "16") (pinfunction "GHC_16") (pintype "output"))
      (node (ref "Q7") (pin "1") (pinfunction "G_1") (pintype "passive"))
    )
    (net (code "13") (name "/GLA") (class "Default")
      (node (ref "IC5") (pin "8") (pinfunction "GLA_8") (pintype "output"))
      (node (ref "Q8") (pin "1") (pinfunction "G_1") (pintype "passive"))
    )
    (net (code "14") (name "/GLB") (class "Default")
      (node (ref "IC5") (pin "13") (pinfunction "GLB_13") (pintype "output"))
      (node (ref "Q9") (pin "1") (pinfunction "G_1") (pintype "passive"))
    )
    (net (code "15") (name "/GLC") (class "Default")
      (node (ref "IC5") (pin "18") (pinfunction "GLC_18") (pintype "output"))
      (node (ref "Q10") (pin "1") (pinfunction "G_1") (pintype "passive"))
    )
    (net (code "16") (name "/INHA") (class "Default")
      (node (ref "IC1") (pin "11") (pinfunction "IO18_11") (pintype "passive"))
      (node (ref "IC5") (pin "34") (pinfunction "INHA_34") (pintype "input"))
    )
    (net (code "17") (name "/INHB") (class "Default")
      (node (ref "IC1") (pin "15") (pinfunction "IO3_15") (pintype "passive"))
      (node (ref "IC5") (pin "36") (pinfunction "INHB_36") (pintype "input"))
    )
    (net (code "18") (name "/INHC") (class "Default")
      (node (ref "IC1") (pin "18") (pinfunction "IO10_18") (pintype "passive"))
      (node (ref "IC5") (pin "38") (pinfunction "INHC_38") (pintype "input"))
    )
    (net (code "19") (name "/INLA") (class "Default")
      (node (ref "IC1") (pin "12") (pinfunction "IO8_12") (pintype "passive"))
      (node (ref "IC5") (pin "35") (pinfunction "INLA_35") (pintype "input"))
    )
    (net (code "20") (name "/INLB") (class "Default")
      (node (ref "IC1") (pin "17") (pinfunction "IO9_17") (pintype "passive"))
      (node (ref "IC5") (pin "37") (pinfunction "INLB_37") (pintype "input"))
    )
    (net (code "21") (name "/INLC") (class "Default")
      (node (ref "IC1") (pin "19") (pinfunction "IO11_19") (pintype "passive"))
      (node (ref "IC5") (pin "39") (pinfunction "INLC_39") (pintype "input"))
    )
    (net (code "22") (name "/IO0") (class "Default")
      (node (ref "C6") (pin "2") (pinfunction "2_2") (pintype "passive"))
      (node (ref "IC1") (pin "27") (pinfunction "IO0_27") (pintype "passive"))
      (node (ref "R2") (pin "2") (pinfunction "2_2") (pintype "passive"))
      (node (ref "S1") (pin "1") (pinfunction "1_1") (pintype "passive"))
      (node (ref "S1") (pin "3") (pinfunction "3_3") (pintype "passive"))
    )
    (net (code "23") (name "/MISO_DRV") (class "Default")
      (node (ref "IC1") (pin "5") (pinfunction "IO5_5") (pintype "passive"))
      (node (ref "IC5") (pin "26") (pinfunction "SDO_26") (pintype "passive"))
    )
    (net (code "24") (name "/MOSI_DRV") (class "Default")
      (node (ref "IC1") (pin "6") (pinfunction "IO6_6") (pintype "passive"))
      (node (ref "IC5") (pin "27") (pinfunction "SDI_27") (pintype "input"))
    )
    (net (code "25") (name "/NFAULT") (class "Default")
      (node (ref "IC1") (pin "32") (pinfunction "IO39_32") (pintype "passive"))
      (node (ref "IC5") (pin "25") (pinfunction "NFAULT_25") (pintype "passive"))
      (node (ref "R25") (pin "1") (pinfunction "1_1") (pintype "passive"))
    )
    (net (code "26") (name "/PWM_Servo") (class "Default")
      (node (ref "IC1") (pin "26") (pinfunction "IO45_26") (pintype "passive"))
    )
    (net (code "27") (name "/RESET") (class "Default")
      (node (ref "IC1") (pin "23") (pinfunction "IO21_23") (pintype "passive"))
      (node (ref "IC6") (pin "6") (pinfunction "RESET_6") (pintype "passive"))
      (node (ref "R26") (pin "2") (pinfunction "2_2") (pintype "passive"))
    )
    (net (code "28") (name "/RXD") (class "Default")
      (node (ref "IC1") (pin "36") (pinfunction "RXD0_36") (pintype "passive"))
    )
    (net (code "29") (name "/SCL") (class "Default")
      (node (ref "IC1") (pin "22") (pinfunction "IO14_22") (pintype "passive"))
      (node (ref "IC6") (pin "7") (pinfunction "SCL_7") (pintype "passive"))
      (node (ref "R9") (pin "2") (pinfunction "2_2") (pintype "passive"))
    )
    (net (code "30") (name "/SCLK") (class "Default")
      (node (ref "IC1") (pin "7") (pinfunction "IO7_7") (pintype "passive"))
      (node (ref "IC5") (pin "28") (pinfunction "SCLK_28") (pintype "input"))
    )
    (net (code "31") (name "/SDA") (class "Default")
      (node (ref "IC1") (pin "21") (pinfunction "IO13_21") (pintype "passive"))
      (node (ref "IC6") (pin "8") (pinfunction "SDA_8") (pintype "passive"))
      (node (ref "R11") (pin "2") (pinfunction "2_2") (pintype "passive"))
    )
    (net (code "32") (name "/SHA") (class "Default")
      (node (ref "IC5") (pin "7") (pinfunction "SHA_7") (pintype "input"))
      (node (ref "Q5") (pin "3") (pinfunction "S_3") (pintype "passive"))
      (node (ref "Q8") (pin "2") (pinfunction "D_2") (pintype "passive"))
    )
    (net (code "33") (name "/SHB") (class "Default")
      (node (ref "IC5") (pin "14") (pinfunction "SHB_14") (pintype "input"))
      (node (ref "Q6") (pin "3") (pinfunction "S_3") (pintype "passive"))
      (node (ref "Q9") (pin "2") (pinfunction "D_2") (pintype "passive"))
    )
    (net (code "34") (name "/SHC") (class "Default")
      (node (ref "IC5") (pin "17") (pinfunction "SHC_17") (pintype "input"))
      (node (ref "Q10") (pin "2") (pinfunction "D_2") (pintype "passive"))
      (node (ref "Q7") (pin "3") (pinfunction "S_3") (pintype "passive"))
    )
    (net (code "35") (name "/SOA") (class "Default")
      (node (ref "IC1") (pin "33") (pinfunction "IO40_33") (pintype "passive"))
      (node (ref "IC5") (pin "23") (pinfunction "SOA_23") (pintype "output"))
    )
    (net (code "36") (name "/SOB") (class "Default")
      (node (ref "IC1") (pin "34") (pinfunction "IO41_34") (pintype "passive"))
      (node (ref "IC5") (pin "22") (pinfunction "SOB_22") (pintype "output"))
    )
    (net (code "37") (name "/SOC") (class "Default")
      (node (ref "IC1") (pin "35") (pinfunction "IO42_35") (pintype "passive"))
      (node (ref "IC5") (pin "21") (pinfunction "SOC_21") (pintype "output"))
    )
    (net (code "38") (name "/SPA") (class "Default")
      (node (ref "IC5") (pin "9") (pinfunction "SPA_9") (pintype "input"))
      (node (ref "Q8") (pin "3") (pinfunction "S_3") (pintype "passive"))
      (node (ref "R27") (pin "2") (pinfunction "2_2") (pintype "passive"))
    )
    (net (code "39") (name "/SPB") (class "Default")
      (node (ref "IC5") (pin "12") (pinfunction "SPB_12") (pintype "input"))
      (node (ref "Q9") (pin "3") (pinfunction "S_3") (pintype "passive"))
      (node (ref "R28") (pin "2") (pinfunction "2_2") (pintype "passive"))
    )
    (net (code "40") (name "/SPC") (class "Default")
      (node (ref "IC5") (pin "19") (pinfunction "SPC_19") (pintype "input"))
      (node (ref "Q10") (pin "3") (pinfunction "S_3") (pintype "passive"))
      (node (ref "R29") (pin "2") (pinfunction "2_2") (pintype "passive"))
    )
    (net (code "41") (name "/SS") (class "Default")
      (node (ref "IC1") (pin "8") (pinfunction "IO15_8") (pintype "passive"))
      (node (ref "IC5") (pin "29") (pinfunction "NSCS_29") (pintype "input"))
    )
    (net (code "42") (name "/ST") (class "Default")
      (node (ref "IC1") (pin "4") (pinfunction "IO4_4") (pintype "passive"))
      (node (ref "IC4") (pin "9") (pinfunction "ST_9") (pintype "passive"))
      (node (ref "R15") (pin "1") (pinfunction "1_1") (pintype "passive"))
    )
    (net (code "43") (name "/TXD") (class "Default")
      (node (ref "IC1") (pin "37") (pinfunction "TXD0_37") (pintype "passive"))
    )
    (net (code "44") (name "3V3") (class "Default")
      (node (ref "C1") (pin "1") (pinfunction "1_1") (pintype "passive"))
      (node (ref "C2") (pin "1") (pinfunction "1_1") (pintype "passive"))
      (node (ref "C3") (pin "2") (pinfunction "2_2") (pintype "passive"))
      (node (ref "C35") (pin "2") (pinfunction "2_2") (pintype "passive"))
      (node (ref "C4") (pin "2") (pinfunction "2_2") (pintype "passive"))
      (node (ref "IC1") (pin "2") (pinfunction "3V3_2") (pintype "passive"))
      (node (ref "IC5") (pin "24") (pinfunction "VREF_24") (pintype "power_in"))
      (node (ref "IC5") (pin "33") (pinfunction "DVDD_33") (pintype "power_in"))
      (node (ref "L1") (pin "1") (pinfunction "1_1") (pintype "passive"))
      (node (ref "R1") (pin "2") (pinfunction "2_2") (pintype "passive"))
      (node (ref "R11") (pin "1") (pinfunction "1_1") (pintype "passive"))
      (node (ref "R14") (pin "1") (pinfunction "1_1") (pintype "passive"))
      (node (ref "R15") (pin "2") (pinfunction "2_2") (pintype "passive"))
      (node (ref "R2") (pin "1") (pinfunction "1_1") (pintype "passive"))
      (node (ref "R25") (pin "2") (pinfunction "2_2") (pintype "passive"))
      (node (ref "R7") (pin "1") (pinfunction "1_1") (pintype "passive"))
      (node (ref "R9") (pin "1") (pinfunction "1_1") (pintype "passive"))
    )
    (net (code "45") (name "GND") (class "Default")
      (node (ref "C1") (pin "2") (pinfunction "2_2") (pintype "passive"))
      (node (ref "C10") (pin "2") (pinfunction "2_2") (pintype "passive"))
      (node (ref "C12") (pin "1") (pinfunction "1_1") (pintype "passive"))
      (node (ref "C13") (pin "1") (pinfunction "1_1") (pintype "passive"))
      (node (ref "C15") (pin "1") (pinfunction "1_1") (pintype "passive"))
      (node (ref "C16") (pin "1") (pinfunction "1_1") (pintype "passive"))
      (node (ref "C18") (pin "2") (pinfunction "2_2") (pintype "passive"))
      (node (ref "C2") (pin "2") (pinfunction "2_2") (pintype "passive"))
      (node (ref "C20") (pin "2") (pinfunction "2_2") (pintype "passive"))
      (node (ref "C21") (pin "2") (pinfunction "2_2") (pintype "passive"))
      (node (ref "C22") (pin "1") (pinfunction "1_1") (pintype "passive"))
      (node (ref "C23") (pin "2") (pinfunction "2_2") (pintype "passive"))
      (node (ref "C24") (pin "2") (pinfunction "2_2") (pintype "passive"))
      (node (ref "C25") (pin "2") (pinfunction "2_2") (pintype "passive"))
      (node (ref "C26") (pin "2") (pinfunction "2_2") (pintype "passive"))
      (node (ref "C27") (pin "2") (pinfunction "2_2") (pintype "passive"))
      (node (ref "C28") (pin "2") (pinfunction "2_2") (pintype "passive"))
      (node (ref "C29") (pin "1") (pinfunction "1_1") (pintype "passive"))
      (node (ref "C3") (pin "1") (pinfunction "1_1") (pintype "passive"))
      (node (ref "C30") (pin "1") (pinfunction "1_1") (pintype "passive"))
      (node (ref "C33") (pin "1") (pinfunction "1_1") (pintype "passive"))
      (node (ref "C34") (pin "1") (pinfunction "1_1") (pintype "passive"))
      (node (ref "C35") (pin "1") (pinfunction "1_1") (pintype "passive"))
      (node (ref "C36") (pin "1") (pinfunction "1_1") (pintype "passive"))
      (node (ref "C4") (pin "1") (pinfunction "1_1") (pintype "passive"))
      (node (ref "C6") (pin "1") (pinfunction "1_1") (pintype "passive"))
      (node (ref "C7") (pin "1") (pinfunction "1_1") (pintype "passive"))
      (node (ref "C8") (pin "1") (pinfunction "1_1") (pintype "passive"))
      (node (ref "C9") (pin "1") (pinfunction "1_1") (pintype "passive"))
      (node (ref "D2") (pin "2") (pinfunction "A_2") (pintype "passive"))
      (node (ref "D3") (pin "2") (pinfunction "A_2") (pintype "passive"))
      (node (ref "IC1") (pin "1") (pinfunction "GND_1_1") (pintype "passive"))
      (node (ref "IC1") (pin "40") (pinfunction "GND_2_40") (pintype "passive"))
      (node (ref "IC1") (pin "41") (pinfunction "GND_3_41") (pintype "passive"))
      (node (ref "IC1") (pin "42") (pinfunction "GND_4_42") (pintype "passive"))
      (node (ref "IC1") (pin "43") (pinfunction "GND_5_43") (pintype "passive"))
      (node (ref "IC1") (pin "44") (pinfunction "GND_6_44") (pintype "passive"))
      (node (ref "IC1") (pin "45") (pinfunction "GND_7_45") (pintype "passive"))
      (node (ref "IC1") (pin "46") (pinfunction "GND_8_46") (pintype "passive"))
      (node (ref "IC1") (pin "47") (pinfunction "GND_9_47") (pintype "passive"))
      (node (ref "IC1") (pin "48") (pinfunction "GND_10_48") (pintype "passive"))
      (node (ref "IC1") (pin "49") (pinfunction "GND_11_49") (pintype "passive"))
      (node (ref "IC2") (pin "16") (pinfunction "PGND_16") (pintype "passive"))
      (node (ref "IC2") (pin "8") (pinfunction "AGND_8") (pintype "passive"))
      (node (ref "IC4") (pin "12") (pinfunction "GND_12") (pintype "passive"))
      (node (ref "IC4") (pin "3") (pinfunction "CP2_3") (pintype "passive"))
      (node (ref "IC4") (pin "4") (pinfunction "OV2_4") (pintype "passive"))
      (node (ref "IC4") (pin "5") (pinfunction "OV1_5") (pintype "passive"))
      (node (ref "IC5") (pin "10") (pinfunction "SNA_10") (pintype "input"))
      (node (ref "IC5") (pin "11") (pinfunction "SNB_11") (pintype "input"))
      (node (ref "IC5") (pin "20") (pinfunction "SNC_20") (pintype "input"))
      (node (ref "IC5") (pin "32") (pinfunction "AGND_32") (pintype "power_in"))
      (node (ref "IC5") (pin "40") (pinfunction "PGND_40") (pintype "power_in"))
      (node (ref "IC5") (pin "41") (pinfunction "EP_41") (pintype "power_in"))
      (node (ref "IC6") (pin "10") (pinfunction "GND_10") (pintype "passive"))
      (node (ref "IC6") (pin "12") (pinfunction "ADDR0_12") (pintype "passive"))
      (node (ref "IC6") (pin "13") (pinfunction "ADDR1_13") (pintype "passive"))
      (node (ref "IC6") (pin "22") (pinfunction "VSYS_22") (pintype "passive"))
      (node (ref "IC6") (pin "25") (pinfunction "EP_25") (pintype "passive"))
      (node (ref "J2") (pin "A1_B12") (pinfunction "GND_A_A1_B12") (pintype "power_in"))
      (node (ref "J2") (pin "B1_A12") (pinfunction "GND_B_B1_A12") (pintype "power_in"))
      (node (ref "J2") (pin "SH1") (pinfunction "SHIELD_SH1") (pintype "passive"))
      (node (ref "J2") (pin "SH2") (pinfunction "SHIELD_SH2") (pintype "passive"))
      (node (ref "J2") (pin "SH3") (pinfunction "SHIELD_SH3") (pintype "passive"))
      (node (ref "J2") (pin "SH4") (pinfunction "SHIELD_SH4") (pintype "passive"))
      (node (ref "PS1") (pin "1") (pinfunction "GND_1") (pintype "power_in"))
      (node (ref "Q2") (pin "3") (pinfunction "S_3") (pintype "passive"))
      (node (ref "R16") (pin "1") (pinfunction "1_1") (pintype "passive"))
      (node (ref "R24") (pin "1") (pinfunction "1_1") (pintype "passive"))
      (node (ref "R26") (pin "1") (pinfunction "1_1") (pintype "passive"))
      (node (ref "R27") (pin "1") (pinfunction "1_1") (pintype "passive"))
      (node (ref "R28") (pin "1") (pinfunction "1_1") (pintype "passive"))
      (node (ref "R29") (pin "1") (pinfunction "1_1") (pintype "passive"))
      (node (ref "R38") (pin "1") (pinfunction "1_1") (pintype "passive"))
      (node (ref "R4") (pin "1") (pinfunction "1_1") (pintype "passive"))
      (node (ref "R5") (pin "1") (pinfunction "1_1") (pintype "passive"))
      (node (ref "S1") (pin "2") (pinfunction "2_2") (pintype "passive"))
      (node (ref "S1") (pin "4") (pinfunction "4_4") (pintype "passive"))
      (node (ref "S2") (pin "1") (pinfunction "1_1") (pintype "passive"))
      (node (ref "S2") (pin "3") (pinfunction "3_3") (pintype "passive"))
    )
    (net (code "46") (name "Net-(C19-Pad2)") (class "Default")
      (node (ref "C19") (pin "2") (pinfunction "2_2") (pintype "passive"))
      (node (ref "R21") (pin "1") (pinfunction "1_1") (pintype "passive"))
    )
    (net (code "47") (name "Net-(D1-K)") (class "Default")
      (node (ref "C25") (pin "1") (pinfunction "1_1") (pintype "passive"))
      (node (ref "D1") (pin "1") (pinfunction "K_1") (pintype "passive"))
      (node (ref "R18") (pin "1") (pinfunction "1_1") (pintype "passive"))
      (node (ref "R22") (pin "2") (pinfunction "2_2") (pintype "passive"))
    )
    (net (code "48") (name "Net-(D3-K)") (class "Default")
      (node (ref "C19") (pin "1") (pinfunction "1_1") (pintype "passive"))
      (node (ref "D3") (pin "1") (pinfunction "K_1") (pintype "passive"))
      (node (ref "Q4") (pin "2") (pinfunction "D_2") (pintype "passive"))
      (node (ref "R20") (pin "2") (pinfunction "2_2") (pintype "passive"))
      (node (ref "R33") (pin "2") (pinfunction "2_2") (pintype "passive"))
    )
    (net (code "49") (name "Net-(IC1-IO48)") (class "Default")
      (node (ref "C36") (pin "2") (pinfunction "2_2") (pintype "passive"))
      (node (ref "IC1") (pin "25") (pinfunction "IO48_25") (pintype "passive"))
      (node (ref "R37") (pin "1") (pinfunction "1_1") (pintype "passive"))
      (node (ref "R38") (pin "2") (pinfunction "2_2") (pintype "passive"))
    )
    (net (code "50") (name "Net-(IC2-BST)") (class "Default")
      (node (ref "C11") (pin "2") (pinfunction "2_2") (pintype "passive"))
      (node (ref "IC2") (pin "15") (pinfunction "BST_15") (pintype "passive"))
      (node (ref "L2") (pin "2") (pinfunction "2_2") (pintype "passive"))
    )
    (net (code "51") (name "Net-(IC2-CSP)") (class "Default")
      (node (ref "IC2") (pin "10") (pinfunction "CSP_10") (pintype "passive"))
      (node (ref "L2") (pin "1") (pinfunction "1_1") (pintype "passive"))
      (node (ref "R6") (pin "1") (pinfunction "1_1") (pintype "passive"))
    )
    (net (code "52") (name "Net-(IC2-NTC)") (class "Default")
      (node (ref "IC2") (pin "13") (pinfunction "NTC_13") (pintype "passive"))
      (node (ref "R3") (pin "1") (pinfunction "1_1") (pintype "passive"))
      (node (ref "R4") (pin "2") (pinfunction "2_2") (pintype "passive"))
    )
    (net (code "53") (name "Net-(IC2-SW)") (class "Default")
      (node (ref "C11") (pin "1") (pinfunction "1_1") (pintype "passive"))
      (node (ref "IC2") (pin "1") (pinfunction "SW_1") (pintype "passive"))
    )
    (net (code "54") (name "Net-(IC2-TMR)") (class "Default")
      (node (ref "C7") (pin "2") (pinfunction "2_2") (pintype "passive"))
      (node (ref "IC2") (pin "14") (pinfunction "TMR_14") (pintype "passive"))
    )
    (net (code "55") (name "Net-(IC2-VCC)") (class "Default")
      (node (ref "C9") (pin "2") (pinfunction "2_2") (pintype "passive"))
      (node (ref "IC2") (pin "3") (pinfunction "VCC_3") (pintype "passive"))
      (node (ref "R3") (pin "2") (pinfunction "2_2") (pintype "passive"))
    )
    (net (code "56") (name "Net-(IC2-VIN)") (class "Default")
      (node (ref "C12") (pin "2") (pinfunction "2_2") (pintype "passive"))
      (node (ref "C13") (pin "2") (pinfunction "2_2") (pintype "passive"))
      (node (ref "IC2") (pin "2") (pinfunction "VIN_2") (pintype "passive"))
      (node (ref "LED1") (pin "2") (pinfunction "A_2") (pintype "passive"))
      (node (ref "R30") (pin "2") (pinfunction "2_2") (pintype "passive"))
    )
    (net (code "57") (name "Net-(IC2-~{CHGOK})") (class "Default")
      (node (ref "IC2") (pin "11") (pinfunction "~{CHGOK}_11") (pintype "passive"))
      (node (ref "R8") (pin "1") (pinfunction "1_1") (pintype "passive"))
    )
    (net (code "58") (name "Net-(IC3-CO)") (class "Default")
      (node (ref "IC3") (pin "3") (pinfunction "CO_3") (pintype "passive"))
      (node (ref "Q2") (pin "1") (pinfunction "G_1") (pintype "passive"))
    )
    (net (code "59") (name "Net-(IC3-CTL)") (class "Default")
      (node (ref "IC3") (pin "1") (pinfunction "CTL_1") (pintype "passive"))
      (node (ref "R12") (pin "1") (pinfunction "1_1") (pintype "passive"))
    )
    (net (code "60") (name "Net-(IC3-DO)") (class "Default")
      (node (ref "IC3") (pin "4") (pinfunction "DO_4") (pintype "passive"))
      (node (ref "Q1") (pin "1") (pinfunction "G_1") (pintype "passive"))
    )
    (net (code "61") (name "Net-(IC3-EP)") (class "Default")
      (node (ref "C14") (pin "2") (pinfunction "2_2") (pintype "passive"))
      (node (ref "IC3") (pin "8") (pinfunction "VDD_8") (pintype "passive"))
      (node (ref "IC3") (pin "9") (pinfunction "EP_9") (pintype "passive"))
      (node (ref "R10") (pin "1") (pinfunction "1_1") (pintype "passive"))
    )
    (net (code "62") (name "Net-(IC3-VC)") (class "Default")
      (node (ref "C17") (pin "2") (pinfunction "2_2") (pintype "passive"))
      (node (ref "IC3") (pin "7") (pinfunction "VC_7") (pintype "passive"))
      (node (ref "R13") (pin "1") (pinfunction "1_1") (pintype "passive"))
    )
    (net (code "63") (name "Net-(IC3-VINI)") (class "Default")
      (node (ref "IC3") (pin "5") (pinfunction "VINI_5") (pintype "passive"))
      (node (ref "Q1") (pin "3") (pinfunction "S_3") (pintype "passive"))
      (node (ref "R17") (pin "1") (pinfunction "1_1") (pintype "passive"))
    )
    (net (code "64") (name "Net-(IC3-VM)") (class "Default")
      (node (ref "IC3") (pin "2") (pinfunction "VM_2") (pintype "passive"))
      (node (ref "R16") (pin "2") (pinfunction "2_2") (pintype "passive"))
    )
    (net (code "65") (name "Net-(IC4-ILIM)") (class "Default")
      (node (ref "IC4") (pin "10") (pinfunction "ILIM_10") (pintype "passive"))
      (node (ref "R24") (pin "2") (pinfunction "2_2") (pintype "passive"))
    )
    (net (code "66") (name "Net-(IC4-IN1)") (class "Default")
      (node (ref "C20") (pin "1") (pinfunction "1_1") (pintype "passive"))
      (node (ref "C21") (pin "1") (pinfunction "1_1") (pintype "passive"))
      (node (ref "IC4") (pin "6") (pinfunction "PR1_6") (pintype "passive"))
      (node (ref "IC4") (pin "7") (pinfunction "IN1_7") (pintype "passive"))
      (node (ref "R32") (pin "1") (pinfunction "1_1") (pintype "passive"))
    )
    (net (code "67") (name "Net-(IC4-IN2)") (class "Default")
      (node (ref "C27") (pin "1") (pinfunction "1_1") (pintype "passive"))
      (node (ref "C28") (pin "1") (pinfunction "1_1") (pintype "passive"))
      (node (ref "IC4") (pin "2") (pinfunction "IN2_2") (pintype "passive"))
      (node (ref "R35") (pin "2") (pinfunction "2_2") (pintype "passive"))
    )
    (net (code "68") (name "Net-(IC4-OUT_1)") (class "Default")
      (node (ref "C23") (pin "1") (pinfunction "1_1") (pintype "passive"))
      (node (ref "C24") (pin "1") (pinfunction "1_1") (pintype "passive"))
      (node (ref "IC4") (pin "1") (pinfunction "OUT_1_1") (pintype "passive"))
      (node (ref "IC4") (pin "8") (pinfunction "OUT_2_8") (pintype "passive"))
      (node (ref "R34") (pin "2") (pinfunction "2_2") (pintype "passive"))
    )
    (net (code "69") (name "Net-(IC4-SS)") (class "Default")
      (node (ref "C30") (pin "2") (pinfunction "2_2") (pintype "passive"))
      (node (ref "IC4") (pin "11") (pinfunction "SS_11") (pintype "passive"))
    )
    (net (code "70") (name "Net-(IC5-CPH)") (class "Default")
      (node (ref "C31") (pin "1") (pinfunction "1_1") (pintype "passive"))
      (node (ref "IC5") (pin "2") (pinfunction "CPH_2") (pintype "power_in"))
    )
    (net (code "71") (name "Net-(IC5-CPL)") (class "Default")
      (node (ref "C31") (pin "2") (pinfunction "2_2") (pintype "passive"))
      (node (ref "IC5") (pin "1") (pinfunction "CPL_1") (pintype "power_in"))
    )
    (net (code "72") (name "Net-(IC5-VCP)") (class "Default")
      (node (ref "C32") (pin "2") (pinfunction "2_2") (pintype "passive"))
      (node (ref "IC5") (pin "3") (pinfunction "VCP_3") (pintype "power_in"))
    )
    (net (code "73") (name "Net-(IC6-DISCH)") (class "Default")
      (node (ref "IC6") (pin "9") (pinfunction "DISCH_9") (pintype "passive"))
      (node (ref "R20") (pin "1") (pinfunction "1_1") (pintype "passive"))
    )
    (net (code "74") (name "Net-(IC6-VBUS_EN_SNK)") (class "Default")
      (node (ref "IC6") (pin "16") (pinfunction "VBUS_EN_SNK_16") (pintype "passive"))
      (node (ref "R22") (pin "1") (pinfunction "1_1") (pintype "passive"))
    )
    (net (code "75") (name "Net-(IC6-VBUS_VS_DISCH)") (class "Default")
      (node (ref "IC6") (pin "18") (pinfunction "VBUS_VS_DISCH_18") (pintype "passive"))
      (node (ref "R23") (pin "1") (pinfunction "1_1") (pintype "passive"))
    )
    (net (code "76") (name "Net-(IC6-VDD)") (class "Default")
      (node (ref "C22") (pin "2") (pinfunction "2_2") (pintype "passive"))
      (node (ref "IC6") (pin "24") (pinfunction "VDD_24") (pintype "passive"))
      (node (ref "Q3") (pin "3") (pinfunction "S_3") (pintype "passive"))
      (node (ref "Q4") (pin "3") (pinfunction "S_3") (pintype "passive"))
      (node (ref "R19") (pin "2") (pinfunction "2_2") (pintype "passive"))
    )
    (net (code "77") (name "Net-(IC6-VREG_1V2)") (class "Default")
      (node (ref "C29") (pin "2") (pinfunction "2_2") (pintype "passive"))
      (node (ref "IC6") (pin "21") (pinfunction "VREG_1V2_21") (pintype "passive"))
    )
    (net (code "78") (name "Net-(IC6-VREG_2V7)") (class "Default")
      (node (ref "C26") (pin "1") (pinfunction "1_1") (pintype "passive"))
      (node (ref "IC6") (pin "23") (pinfunction "VREG_2V7_23") (pintype "passive"))
    )
    (net (code "79") (name "Net-(IC7-CD)") (class "Default")
      (node (ref "C39") (pin "2") (pinfunction "2_2") (pintype "passive"))
      (node (ref "IC7") (pin "4") (pinfunction "CD_4") (pintype "passive"))
    )
    (net (code "80") (name "Net-(IC7-VC1)") (class "Default")
      (node (ref "C37") (pin "1") (pinfunction "1_1") (pintype "passive"))
      (node (ref "C38") (pin "2") (pinfunction "2_2") (pintype "passive"))
      (node (ref "IC7") (pin "2") (pinfunction "VC1_2") (pintype "passive"))
      (node (ref "R41") (pin "1") (pinfunction "1_1") (pintype "passive"))
    )
    (net (code "81") (name "Net-(IC7-VC1_CB)") (class "Default")
      (node (ref "IC7") (pin "3") (pinfunction "VC1_CB_3") (pintype "passive"))
      (node (ref "R42") (pin "1") (pinfunction "1_1") (pintype "passive"))
    )
    (net (code "82") (name "Net-(IC7-VC2)") (class "Default")
      (node (ref "C37") (pin "2") (pinfunction "2_2") (pintype "passive"))
      (node (ref "IC7") (pin "1") (pinfunction "VC2_1") (pintype "passive"))
      (node (ref "R39") (pin "1") (pinfunction "1_1") (pintype "passive"))
    )
    (net (code "83") (name "Net-(IC7-VDD)") (class "Default")
      (node (ref "C40") (pin "2") (pinfunction "2_2") (pintype "passive"))
      (node (ref "IC7") (pin "7") (pinfunction "VDD_7") (pintype "passive"))
      (node (ref "R40") (pin "2") (pinfunction "2_2") (pintype "passive"))
    )
    (net (code "84") (name "Net-(LED1-K)") (class "Default")
      (node (ref "LED1") (pin "1") (pinfunction "K_1") (pintype "passive"))
      (node (ref "R8") (pin "2") (pinfunction "2_2") (pintype "passive"))
    )
    (net (code "85") (name "Net-(PS1-CB)") (class "Default")
      (node (ref "C5") (pin "1") (pinfunction "1_1") (pintype "passive"))
      (node (ref "PS1") (pin "6") (pinfunction "CB_6") (pintype "power_in"))
    )
    (net (code "86") (name "Net-(PS1-FB)") (class "Default")
      (node (ref "PS1") (pin "4") (pinfunction "FB_4") (pintype "input"))
      (node (ref "R1") (pin "1") (pinfunction "1_1") (pintype "passive"))
      (node (ref "R5") (pin "2") (pinfunction "2_2") (pintype "passive"))
    )
    (net (code "87") (name "Net-(PS1-SW)") (class "Default")
      (node (ref "C5") (pin "2") (pinfunction "2_2") (pintype "passive"))
      (node (ref "L1") (pin "2") (pinfunction "2_2") (pintype "passive"))
      (node (ref "PS1") (pin "2") (pinfunction "SW_2") (pintype "power_in"))
    )
    (net (code "88") (name "Net-(Q1-D)") (class "Default")
      (node (ref "Q1") (pin "2") (pinfunction "D_2") (pintype "passive"))
      (node (ref "Q2") (pin "2") (pinfunction "D_2") (pintype "passive"))
    )
    (net (code "89") (name "Net-(Q3-G)") (class "Default")
      (node (ref "Q3") (pin "1") (pinfunction "G_1") (pintype "passive"))
      (node (ref "Q4") (pin "1") (pinfunction "G_1") (pintype "passive"))
      (node (ref "R19") (pin "1") (pinfunction "1_1") (pintype "passive"))
      (node (ref "R21") (pin "2") (pinfunction "2_2") (pintype "passive"))
      (node (ref "R23") (pin "2") (pinfunction "2_2") (pintype "passive"))
    )
    (net (code "90") (name "VBAT+") (class "Default")
      (node (ref "C15") (pin "2") (pinfunction "2_2") (pintype "passive"))
      (node (ref "C16") (pin "2") (pinfunction "2_2") (pintype "passive"))
      (node (ref "IC2") (pin "9") (pinfunction "BATT_9") (pintype "passive"))
      (node (ref "J1") (pin "1") (pinfunction "1_1") (pintype "passive"))
      (node (ref "J3") (pin "1") (pinfunction "1_1") (pintype "passive"))
      (node (ref "R10") (pin "2") (pinfunction "2_2") (pintype "passive"))
      (node (ref "R12") (pin "2") (pinfunction "2_2") (pintype "passive"))
      (node (ref "R31") (pin "1") (pinfunction "1_1") (pintype "passive"))
      (node (ref "R37") (pin "2") (pinfunction "2_2") (pintype "passive"))
      (node (ref "R39") (pin "2") (pinfunction "2_2") (pintype "passive"))
      (node (ref "R40") (pin "1") (pinfunction "1_1") (pintype "passive"))
      (node (ref "R6") (pin "2") (pinfunction "2_2") (pintype "passive"))
    )
    (net (code "91") (name "VBAT-") (class "Default")
      (node (ref "C14") (pin "1") (pinfunction "1_1") (pintype "passive"))
      (node (ref "C17") (pin "1") (pinfunction "1_1") (pintype "passive"))
      (node (ref "C38") (pin "1") (pinfunction "1_1") (pintype "passive"))
      (node (ref "C39") (pin "1") (pinfunction "1_1") (pintype "passive"))
      (node (ref "C40") (pin "1") (pinfunction "1_1") (pintype "passive"))
      (node (ref "IC3") (pin "6") (pinfunction "VSS_6") (pintype "passive"))
      (node (ref "IC7") (pin "5") (pinfunction "GND_1_5") (pintype "passive"))
      (node (ref "IC7") (pin "6") (pinfunction "~{CB_EN}_6") (pintype "passive"))
      (node (ref "IC7") (pin "9") (pinfunction "GND_2_9") (pintype "passive"))
      (node (ref "J1") (pin "3") (pinfunction "3_3") (pintype "passive"))
      (node (ref "J3") (pin "2") (pinfunction "2_2") (pintype "passive"))
      (node (ref "R17") (pin "2") (pinfunction "2_2") (pintype "passive"))
    )
    (net (code "92") (name "VBATJ") (class "Default")
      (node (ref "R31") (pin "2") (pinfunction "2_2") (pintype "passive"))
      (node (ref "R35") (pin "1") (pinfunction "1_1") (pintype "passive"))
      (node (ref "R36") (pin "1") (pinfunction "1_1") (pintype "passive"))
    )
    (net (code "93") (name "VBATM") (class "Default")
      (node (ref "J1") (pin "2") (pinfunction "2_2") (pintype "passive"))
      (node (ref "R13") (pin "2") (pinfunction "2_2") (pintype "passive"))
      (node (ref "R41") (pin "2") (pinfunction "2_2") (pintype "passive"))
      (node (ref "R42") (pin "2") (pinfunction "2_2") (pintype "passive"))
    )
    (net (code "94") (name "VBUS") (class "Default")
      (node (ref "C18") (pin "1") (pinfunction "1_1") (pintype "passive"))
      (node (ref "D1") (pin "2") (pinfunction "A_2") (pintype "passive"))
      (node (ref "D2") (pin "1") (pinfunction "K_1") (pintype "passive"))
      (node (ref "J2") (pin "A4_B9") (pinfunction "VBUS_A_A4_B9") (pintype "power_in"))
      (node (ref "J2") (pin "B4_A9") (pinfunction "VBUS_B_B4_A9") (pintype "power_in"))
      (node (ref "Q3") (pin "2") (pinfunction "D_2") (pintype "passive"))
      (node (ref "R18") (pin "2") (pinfunction "2_2") (pintype "passive"))
    )
    (net (code "95") (name "VDRAIN") (class "Default")
      (node (ref "C32") (pin "1") (pinfunction "1_1") (pintype "passive"))
      (node (ref "C33") (pin "2") (pinfunction "2_2") (pintype "passive"))
      (node (ref "C34") (pin "2") (pinfunction "2_2") (pintype "passive"))
      (node (ref "IC5") (pin "4") (pinfunction "VM_4") (pintype "power_in"))
      (node (ref "IC5") (pin "5") (pinfunction "VDRAIN_5") (pintype "input"))
      (node (ref "Q5") (pin "2") (pinfunction "D_2") (pintype "passive"))
      (node (ref "Q6") (pin "2") (pinfunction "D_2") (pintype "passive"))
      (node (ref "Q7") (pin "2") (pinfunction "D_2") (pintype "passive"))
      (node (ref "R36") (pin "2") (pinfunction "2_2") (pintype "passive"))
    )
    (net (code "96") (name "VMCU") (class "Default")
      (node (ref "C8") (pin "2") (pinfunction "2_2") (pintype "passive"))
      (node (ref "PS1") (pin "3") (pinfunction "VIN_3") (pintype "power_in"))
      (node (ref "PS1") (pin "5") (pinfunction "EN_5") (pintype "input"))
      (node (ref "R34") (pin "1") (pinfunction "1_1") (pintype "passive"))
    )
    (net (code "97") (name "VSYS") (class "Default")
      (node (ref "R30") (pin "1") (pinfunction "1_1") (pintype "passive"))
      (node (ref "R32") (pin "2") (pinfunction "2_2") (pintype "passive"))
      (node (ref "R33") (pin "1") (pinfunction "1_1") (pintype "passive"))
    )
    (net (code "98") (name "unconnected-(IC1-IO1-Pad39)") (class "Default")
      (node (ref "IC1") (pin "39") (pinfunction "IO1_39") (pintype "passive"))
    )
    (net (code "99") (name "unconnected-(IC1-IO2-Pad38)") (class "Default")
      (node (ref "IC1") (pin "38") (pinfunction "IO2_38") (pintype "passive"))
    )
    (net (code "100") (name "unconnected-(IC1-IO35-Pad28)") (class "Default")
      (node (ref "IC1") (pin "28") (pinfunction "IO35_28") (pintype "passive"))
    )
    (net (code "101") (name "unconnected-(IC1-IO36-Pad29)") (class "Default")
      (node (ref "IC1") (pin "29") (pinfunction "IO36_29") (pintype "passive"))
    )
    (net (code "102") (name "unconnected-(IC1-IO37-Pad30)") (class "Default")
      (node (ref "IC1") (pin "30") (pinfunction "IO37_30") (pintype "passive"))
    )
    (net (code "103") (name "unconnected-(IC1-IO38-Pad31)") (class "Default")
      (node (ref "IC1") (pin "31") (pinfunction "IO38_31") (pintype "passive"))
    )
    (net (code "104") (name "unconnected-(IC1-IO46-Pad16)") (class "Default")
      (node (ref "IC1") (pin "16") (pinfunction "IO46_16") (pintype "passive+no_connect"))
    )
    (net (code "105") (name "unconnected-(IC2-CELL-Pad4)") (class "Default")
      (node (ref "IC2") (pin "4") (pinfunction "CELL_4") (pintype "passive+no_connect"))
    )
    (net (code "106") (name "unconnected-(IC2-NC-Pad7)") (class "Default")
      (node (ref "IC2") (pin "7") (pinfunction "NC_7") (pintype "passive+no_connect"))
    )
    (net (code "107") (name "unconnected-(IC2-SEL-Pad5)") (class "Default")
      (node (ref "IC2") (pin "5") (pinfunction "SEL_5") (pintype "passive+no_connect"))
    )
    (net (code "108") (name "unconnected-(IC2-~{ACOK}-Pad12)") (class "Default")
      (node (ref "IC2") (pin "12") (pinfunction "~{ACOK}_12") (pintype "passive+no_connect"))
    )
    (net (code "109") (name "unconnected-(IC6-ATTACH-Pad11)") (class "Default")
      (node (ref "IC6") (pin "11") (pinfunction "ATTACH_11") (pintype "passive+no_connect"))
    )
    (net (code "110") (name "unconnected-(IC6-A_B_SIDE-Pad17)") (class "Default")
      (node (ref "IC6") (pin "17") (pinfunction "A_B_SIDE_17") (pintype "passive+no_connect"))
    )
    (net (code "111") (name "unconnected-(IC6-GPIO-Pad15)") (class "Default")
      (node (ref "IC6") (pin "15") (pinfunction "GPIO_15") (pintype "passive+no_connect"))
    )
    (net (code "112") (name "unconnected-(IC6-NC-Pad3)") (class "Default")
      (node (ref "IC6") (pin "3") (pinfunction "NC_3") (pintype "passive+no_connect"))
    )
    (net (code "113") (name "unconnected-(IC6-POWER_OK2-Pad20)") (class "Default")
      (node (ref "IC6") (pin "20") (pinfunction "POWER_OK2_20") (pintype "passive+no_connect"))
    )
    (net (code "114") (name "unconnected-(IC6-POWER_OK3-Pad14)") (class "Default")
      (node (ref "IC6") (pin "14") (pinfunction "POWER_OK3_14") (pintype "passive+no_connect"))
    )
    (net (code "115") (name "unconnected-(IC7-OUT-Pad8)") (class "Default")
      (node (ref "IC7") (pin "8") (pinfunction "OUT_8") (pintype "passive+no_connect"))
    )
    (net (code "116") (name "unconnected-(J2-SBU1-PadA8)") (class "Default")
      (node (ref "J2") (pin "A8") (pinfunction "SBU1_A8") (pintype "bidirectional+no_connect"))
    )
    (net (code "117") (name "unconnected-(J2-SBU2-PadB8)") (class "Default")
      (node (ref "J2") (pin "B8") (pinfunction "SBU2_B8") (pintype "bidirectional+no_connect"))
    )
  )
)
